# NICBP.net
KiCad netlist of a schematic drawn in EAGLE
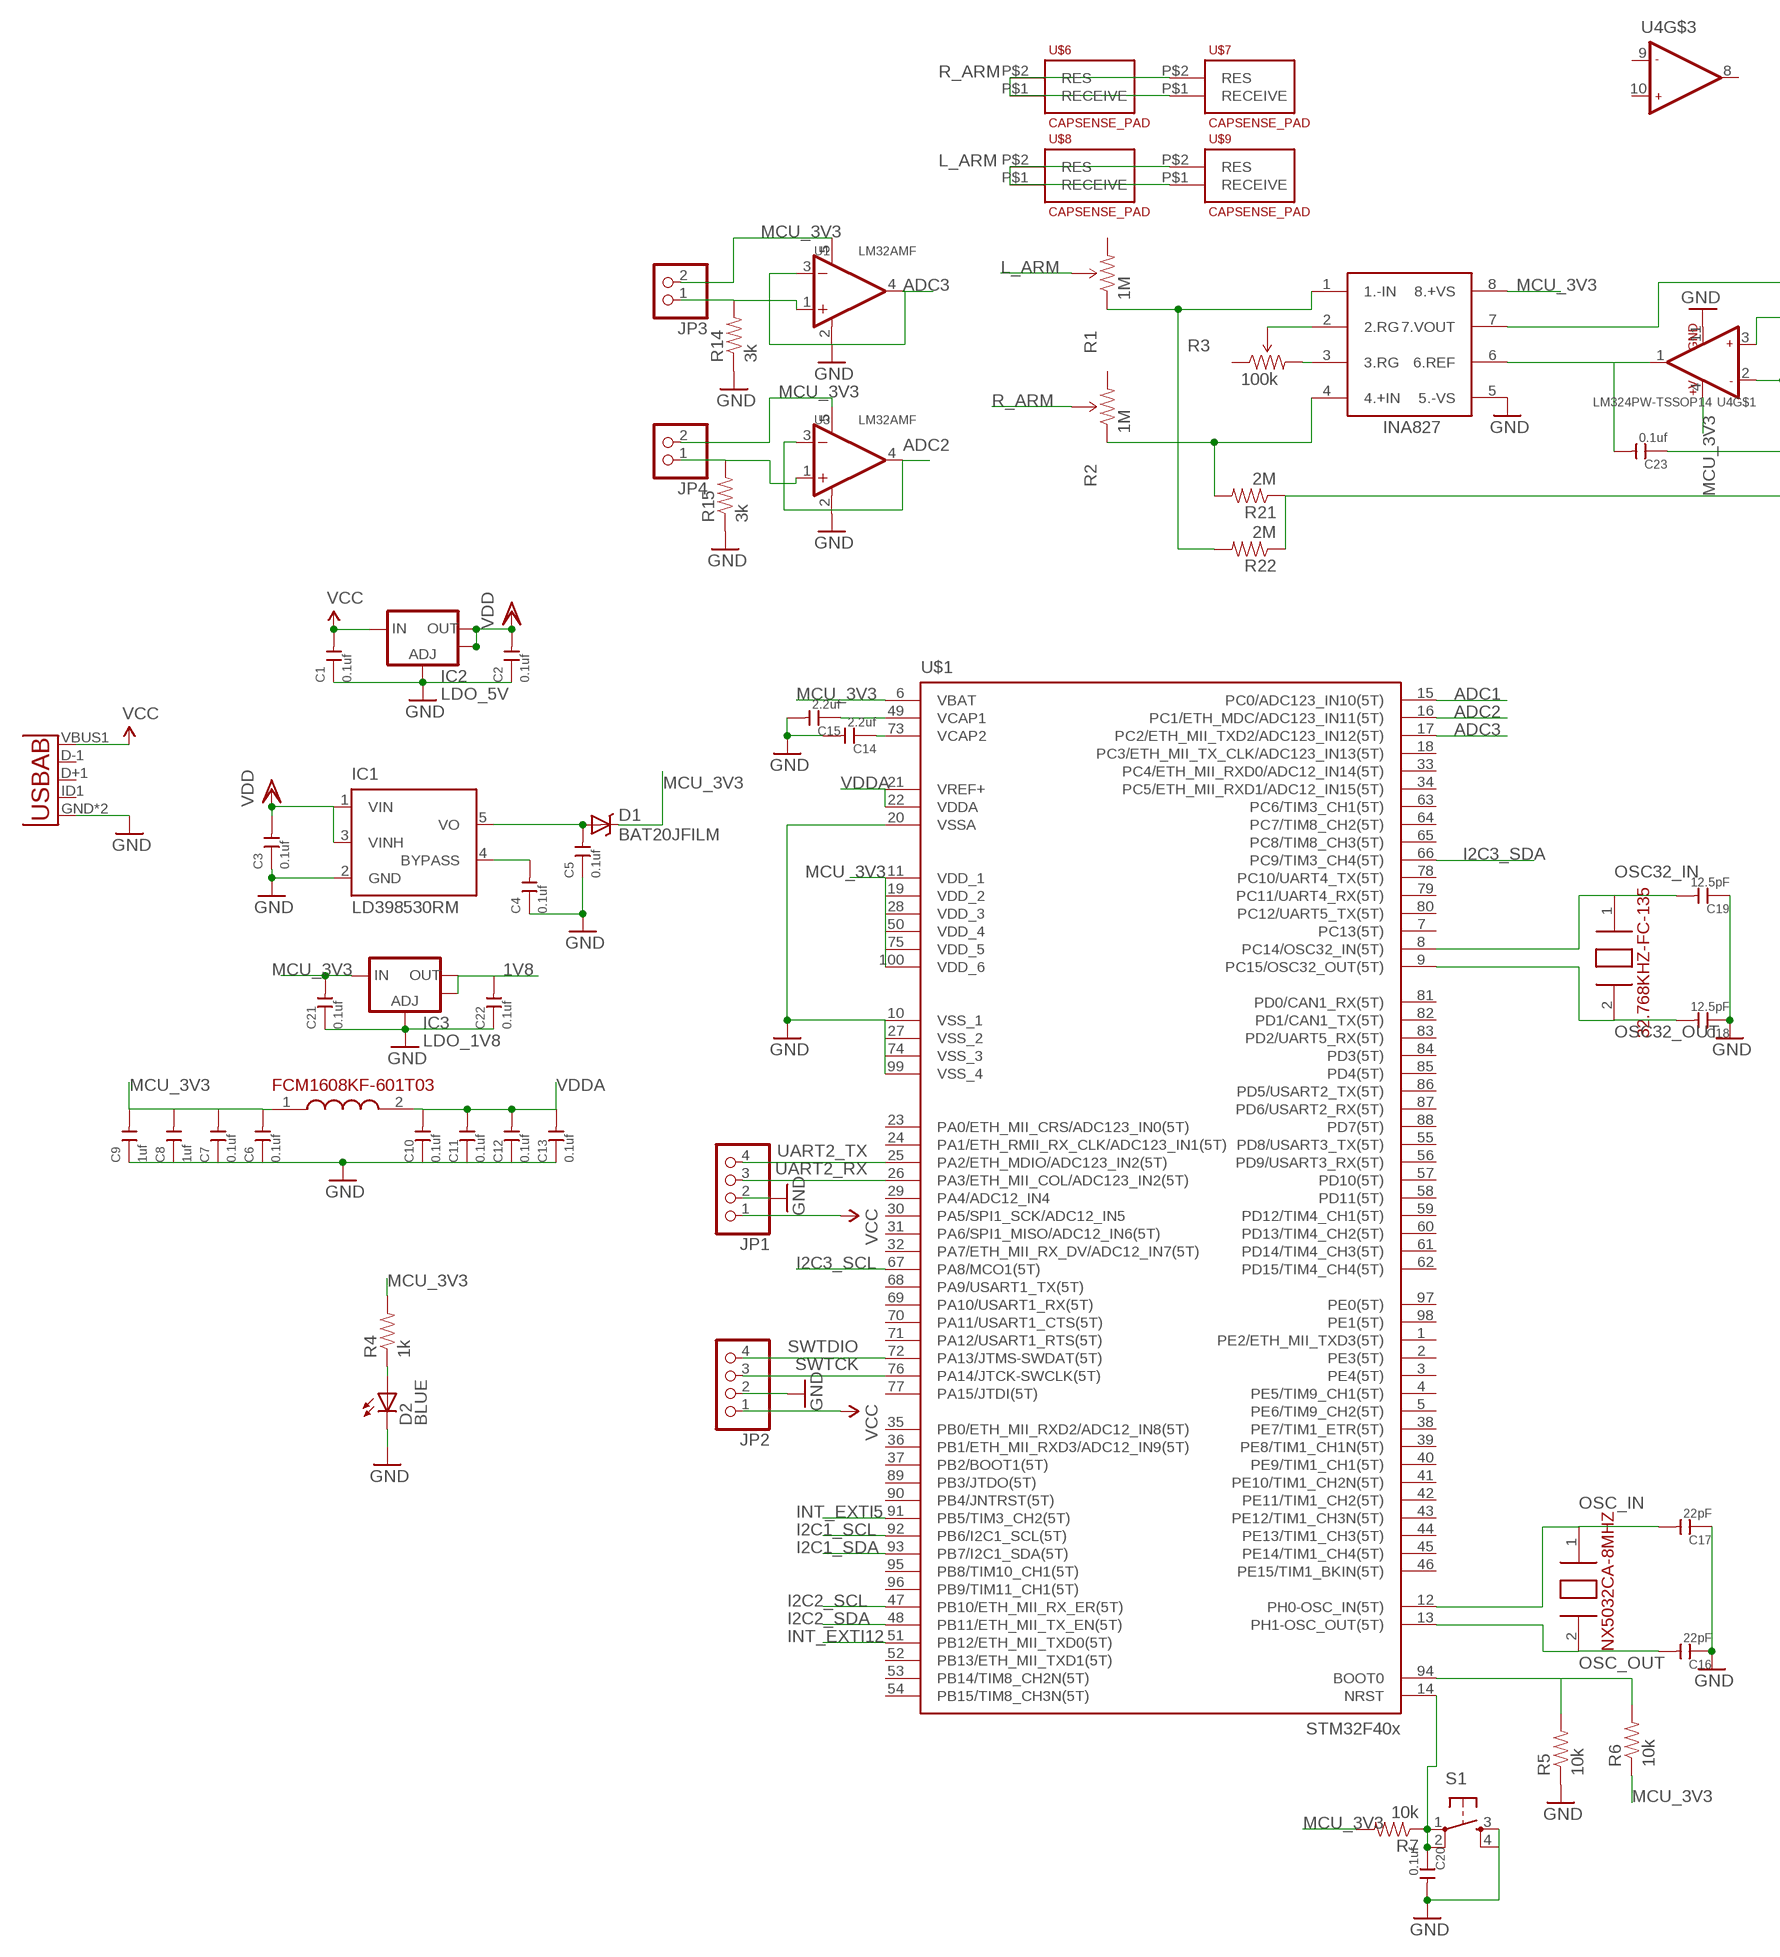
[diagram p0: schematic, sheet 1, part 1 of 2]
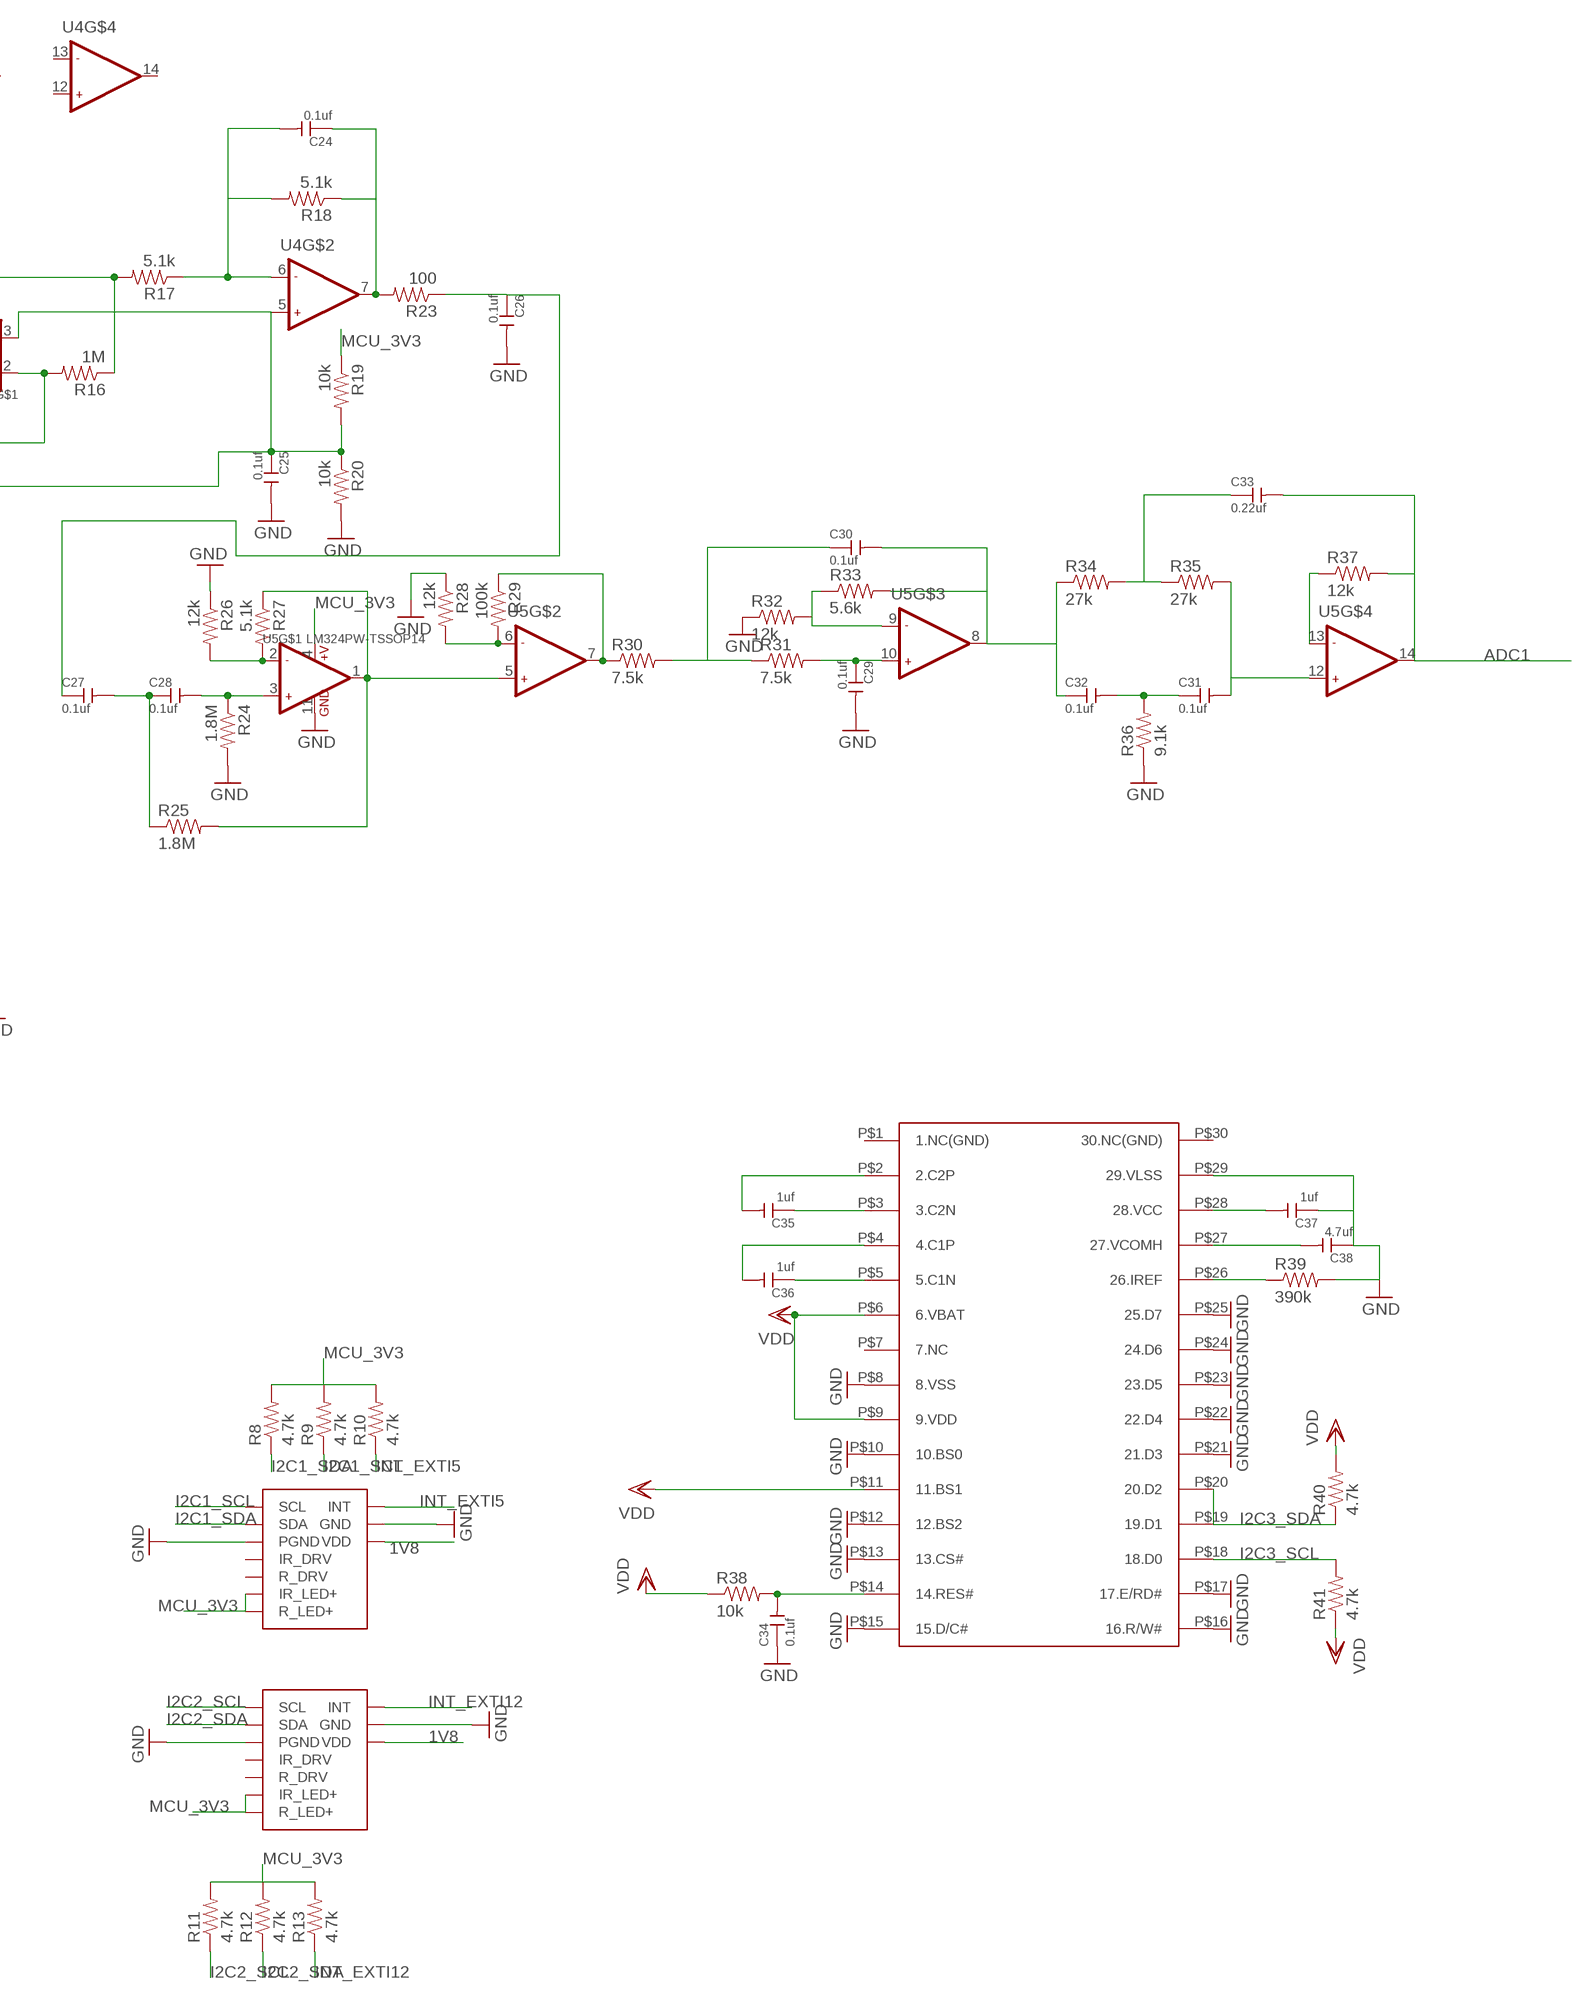
[diagram p1: schematic, sheet 1, part 2 of 2]

(export (version "E")
  (design (tool "Eeschema 10.0.6"))
  (components
    (comp (ref "C1")
      (value "0.1uf")
      (footprint "eagle-import:C0603")
      (fields (field (name "MPN") "CC0603KRX5R6BB475"))
      (libsource (lib "eagle-import") (part "CERAMIC-4.7UF-10V-10%-X5R(0603)"))
    )
    (comp (ref "C2")
      (value "0.1uf")
      (footprint "eagle-import:C0603")
      (fields (field (name "MPN") "CC0603KRX5R6BB475"))
      (libsource (lib "eagle-import") (part "CERAMIC-4.7UF-10V-10%-X5R(0603)"))
    )
    (comp (ref "C3")
      (value "0.1uf")
      (footprint "eagle-import:C0603")
      (fields (field (name "MPN") "CC0603KRX5R6BB475"))
      (libsource (lib "eagle-import") (part "CERAMIC-4.7UF-10V-10%-X5R(0603)"))
    )
    (comp (ref "C4")
      (value "0.1uf")
      (footprint "eagle-import:C0603")
      (fields (field (name "MPN") "CC0603KRX5R6BB475"))
      (libsource (lib "eagle-import") (part "CERAMIC-4.7UF-10V-10%-X5R(0603)"))
    )
    (comp (ref "C5")
      (value "0.1uf")
      (footprint "eagle-import:C0603")
      (fields (field (name "MPN") "CC0603KRX5R6BB475"))
      (libsource (lib "eagle-import") (part "CERAMIC-4.7UF-10V-10%-X5R(0603)"))
    )
    (comp (ref "C6")
      (value "0.1uf")
      (footprint "eagle-import:C0603")
      (fields (field (name "MPN") "CC0603KRX5R6BB475"))
      (libsource (lib "eagle-import") (part "CERAMIC-4.7UF-10V-10%-X5R(0603)"))
    )
    (comp (ref "C7")
      (value "0.1uf")
      (footprint "eagle-import:C0603")
      (fields (field (name "MPN") "CC0603KRX5R6BB475"))
      (libsource (lib "eagle-import") (part "CERAMIC-4.7UF-10V-10%-X5R(0603)"))
    )
    (comp (ref "C8")
      (value "1uf")
      (footprint "eagle-import:C0603")
      (fields (field (name "MPN") "CC0603KRX5R6BB475"))
      (libsource (lib "eagle-import") (part "CERAMIC-4.7UF-10V-10%-X5R(0603)"))
    )
    (comp (ref "C9")
      (value "1uf")
      (footprint "eagle-import:C0603")
      (fields (field (name "MPN") "CC0603KRX5R6BB475"))
      (libsource (lib "eagle-import") (part "CERAMIC-4.7UF-10V-10%-X5R(0603)"))
    )
    (comp (ref "C10")
      (value "0.1uf")
      (footprint "eagle-import:C0603")
      (fields (field (name "MPN") "CC0603KRX5R6BB475"))
      (libsource (lib "eagle-import") (part "CERAMIC-4.7UF-10V-10%-X5R(0603)"))
    )
    (comp (ref "C11")
      (value "0.1uf")
      (footprint "eagle-import:C0603")
      (fields (field (name "MPN") "CC0603KRX5R6BB475"))
      (libsource (lib "eagle-import") (part "CERAMIC-4.7UF-10V-10%-X5R(0603)"))
    )
    (comp (ref "C12")
      (value "0.1uf")
      (footprint "eagle-import:C0603")
      (fields (field (name "MPN") "CC0603KRX5R6BB475"))
      (libsource (lib "eagle-import") (part "CERAMIC-4.7UF-10V-10%-X5R(0603)"))
    )
    (comp (ref "C13")
      (value "0.1uf")
      (footprint "eagle-import:C0603")
      (fields (field (name "MPN") "CC0603KRX5R6BB475"))
      (libsource (lib "eagle-import") (part "CERAMIC-4.7UF-10V-10%-X5R(0603)"))
    )
    (comp (ref "C14")
      (value "2.2uf")
      (footprint "eagle-import:C0603")
      (fields (field (name "MPN") "CC0603KRX5R6BB475"))
      (libsource (lib "eagle-import") (part "CERAMIC-4.7UF-10V-10%-X5R(0603)"))
    )
    (comp (ref "C15")
      (value "2.2uf")
      (footprint "eagle-import:C0603")
      (fields (field (name "MPN") "CC0603KRX5R6BB475"))
      (libsource (lib "eagle-import") (part "CERAMIC-4.7UF-10V-10%-X5R(0603)"))
    )
    (comp (ref "C16")
      (value "22pF")
      (footprint "eagle-import:C0603")
      (fields (field (name "MPN") "CC0603KRX5R6BB475"))
      (libsource (lib "eagle-import") (part "CERAMIC-4.7UF-10V-10%-X5R(0603)"))
    )
    (comp (ref "C17")
      (value "22pF")
      (footprint "eagle-import:C0603")
      (fields (field (name "MPN") "CC0603KRX5R6BB475"))
      (libsource (lib "eagle-import") (part "CERAMIC-4.7UF-10V-10%-X5R(0603)"))
    )
    (comp (ref "C18")
      (value "12.5pF")
      (footprint "eagle-import:C0603")
      (fields (field (name "MPN") "CC0603KRX5R6BB475"))
      (libsource (lib "eagle-import") (part "CERAMIC-4.7UF-10V-10%-X5R(0603)"))
    )
    (comp (ref "C19")
      (value "12.5pF")
      (footprint "eagle-import:C0603")
      (fields (field (name "MPN") "CC0603KRX5R6BB475"))
      (libsource (lib "eagle-import") (part "CERAMIC-4.7UF-10V-10%-X5R(0603)"))
    )
    (comp (ref "C20")
      (value "0.1uf")
      (footprint "eagle-import:C0603")
      (fields (field (name "MPN") "CC0603KRX5R6BB475"))
      (libsource (lib "eagle-import") (part "CERAMIC-4.7UF-10V-10%-X5R(0603)"))
    )
    (comp (ref "C21")
      (value "0.1uf")
      (footprint "eagle-import:C0603")
      (fields (field (name "MPN") "CC0603KRX5R6BB475"))
      (libsource (lib "eagle-import") (part "CERAMIC-4.7UF-10V-10%-X5R(0603)"))
    )
    (comp (ref "C22")
      (value "0.1uf")
      (footprint "eagle-import:C0603")
      (fields (field (name "MPN") "CC0603KRX5R6BB475"))
      (libsource (lib "eagle-import") (part "CERAMIC-4.7UF-10V-10%-X5R(0603)"))
    )
    (comp (ref "C23")
      (value "0.1uf")
      (footprint "eagle-import:C0603")
      (fields (field (name "MPN") "CC0603KRX5R6BB475"))
      (libsource (lib "eagle-import") (part "CERAMIC-4.7UF-10V-10%-X5R(0603)"))
    )
    (comp (ref "C24")
      (value "0.1uf")
      (footprint "eagle-import:C0603")
      (fields (field (name "MPN") "CC0603KRX5R6BB475"))
      (libsource (lib "eagle-import") (part "CERAMIC-4.7UF-10V-10%-X5R(0603)"))
    )
    (comp (ref "C25")
      (value "0.1uf")
      (footprint "eagle-import:C0603")
      (fields (field (name "MPN") "CC0603KRX5R6BB475"))
      (libsource (lib "eagle-import") (part "CERAMIC-4.7UF-10V-10%-X5R(0603)"))
    )
    (comp (ref "C26")
      (value "0.1uf")
      (footprint "eagle-import:C0603")
      (fields (field (name "MPN") "CC0603KRX5R6BB475"))
      (libsource (lib "eagle-import") (part "CERAMIC-4.7UF-10V-10%-X5R(0603)"))
    )
    (comp (ref "C27")
      (value "0.1uf")
      (footprint "eagle-import:C0603")
      (fields (field (name "MPN") "CC0603KRX5R6BB475"))
      (libsource (lib "eagle-import") (part "CERAMIC-4.7UF-10V-10%-X5R(0603)"))
    )
    (comp (ref "C28")
      (value "0.1uf")
      (footprint "eagle-import:C0603")
      (fields (field (name "MPN") "CC0603KRX5R6BB475"))
      (libsource (lib "eagle-import") (part "CERAMIC-4.7UF-10V-10%-X5R(0603)"))
    )
    (comp (ref "C29")
      (value "0.1uf")
      (footprint "eagle-import:C0603")
      (fields (field (name "MPN") "CC0603KRX5R6BB475"))
      (libsource (lib "eagle-import") (part "CERAMIC-4.7UF-10V-10%-X5R(0603)"))
    )
    (comp (ref "C30")
      (value "0.1uf")
      (footprint "eagle-import:C0603")
      (fields (field (name "MPN") "CC0603KRX5R6BB475"))
      (libsource (lib "eagle-import") (part "CERAMIC-4.7UF-10V-10%-X5R(0603)"))
    )
    (comp (ref "C31")
      (value "0.1uf")
      (footprint "eagle-import:C0603")
      (fields (field (name "MPN") "CC0603KRX5R6BB475"))
      (libsource (lib "eagle-import") (part "CERAMIC-4.7UF-10V-10%-X5R(0603)"))
    )
    (comp (ref "C32")
      (value "0.1uf")
      (footprint "eagle-import:C0603")
      (fields (field (name "MPN") "CC0603KRX5R6BB475"))
      (libsource (lib "eagle-import") (part "CERAMIC-4.7UF-10V-10%-X5R(0603)"))
    )
    (comp (ref "C33")
      (value "0.22uf")
      (footprint "eagle-import:C0603")
      (fields (field (name "MPN") "CC0603KRX5R6BB475"))
      (libsource (lib "eagle-import") (part "CERAMIC-4.7UF-10V-10%-X5R(0603)"))
    )
    (comp (ref "C34")
      (value "0.1uf")
      (footprint "eagle-import:C0603")
      (fields (field (name "MPN") "CC0603KRX5R6BB475"))
      (libsource (lib "eagle-import") (part "CERAMIC-4.7UF-10V-10%-X5R(0603)"))
    )
    (comp (ref "C35")
      (value "1uf")
      (footprint "eagle-import:C0603")
      (fields (field (name "MPN") "CC0603KRX5R6BB475"))
      (libsource (lib "eagle-import") (part "CERAMIC-4.7UF-10V-10%-X5R(0603)"))
    )
    (comp (ref "C36")
      (value "1uf")
      (footprint "eagle-import:C0603")
      (fields (field (name "MPN") "CC0603KRX5R6BB475"))
      (libsource (lib "eagle-import") (part "CERAMIC-4.7UF-10V-10%-X5R(0603)"))
    )
    (comp (ref "C37")
      (value "1uf")
      (footprint "eagle-import:C0603")
      (fields (field (name "MPN") "CC0603KRX5R6BB475"))
      (libsource (lib "eagle-import") (part "CERAMIC-4.7UF-10V-10%-X5R(0603)"))
    )
    (comp (ref "C38")
      (value "4.7uf")
      (footprint "eagle-import:C0603")
      (fields (field (name "MPN") "CC0603KRX5R6BB475"))
      (libsource (lib "eagle-import") (part "CERAMIC-4.7UF-10V-10%-X5R(0603)"))
    )
    (comp (ref "D1")
      (value "BAT20JFILM")
      (footprint "eagle-import:SOD-323")
      (libsource (lib "eagle-import") (part "BAT20JFILM"))
    )
    (comp (ref "D2")
      (value "BLUE")
      (footprint "eagle-import:LED-0603")
      (libsource (lib "eagle-import") (part "LED-BLUE0603"))
    )
    (comp (ref "IC1")
      (value "LD398530RM")
      (footprint "eagle-import:SOT23-5L")
      (libsource (lib "eagle-import") (part "LD3985M30R"))
    )
    (comp (ref "IC2")
      (value "LDO_5V")
      (footprint "eagle-import:SOT223")
      (libsource (lib "eagle-import") (part "V_REG_LM1117SOT223"))
    )
    (comp (ref "IC3")
      (value "LDO_1V8")
      (footprint "eagle-import:SOT223")
      (libsource (lib "eagle-import") (part "V_REG_LM1117SOT223"))
    )
    (comp (ref "JP1")
      (value "PINHD-1X4")
      (footprint "eagle-import:1X04")
      (libsource (lib "eagle-import") (part "PINHD-1X4"))
    )
    (comp (ref "JP2")
      (value "PINHD-1X4")
      (footprint "eagle-import:1X04")
      (libsource (lib "eagle-import") (part "PINHD-1X4"))
    )
    (comp (ref "JP3")
      (value "PINHD-1X2")
      (footprint "eagle-import:1X02")
      (libsource (lib "eagle-import") (part "PINHD-1X2"))
    )
    (comp (ref "JP4")
      (value "PINHD-1X2")
      (footprint "eagle-import:1X02")
      (libsource (lib "eagle-import") (part "PINHD-1X2"))
    )
    (comp (ref "R1")
      (value "1M")
      (footprint "eagle-import:TRIMPOT_TC33")
      (libsource (lib "eagle-import") (part "TRIMPOT-2"))
    )
    (comp (ref "R2")
      (value "1M")
      (footprint "eagle-import:TRIMPOT_TC33")
      (libsource (lib "eagle-import") (part "TRIMPOT-2"))
    )
    (comp (ref "R3")
      (value "100k")
      (footprint "eagle-import:TRIMPOT_TC33")
      (libsource (lib "eagle-import") (part "TRIMPOT-2"))
    )
    (comp (ref "R4")
      (value "1k")
      (footprint "eagle-import:0603")
      (libsource (lib "eagle-import") (part "0OHM1/10W5%(0603)"))
    )
    (comp (ref "R5")
      (value "10k")
      (footprint "eagle-import:0603")
      (libsource (lib "eagle-import") (part "0OHM1/10W5%(0603)"))
    )
    (comp (ref "R6")
      (value "10k")
      (footprint "eagle-import:0603")
      (libsource (lib "eagle-import") (part "0OHM1/10W5%(0603)"))
    )
    (comp (ref "R7")
      (value "10k")
      (footprint "eagle-import:0603")
      (libsource (lib "eagle-import") (part "0OHM1/10W5%(0603)"))
    )
    (comp (ref "R8")
      (value "4.7k")
      (footprint "eagle-import:0603")
      (libsource (lib "eagle-import") (part "0OHM1/10W5%(0603)"))
    )
    (comp (ref "R9")
      (value "4.7k")
      (footprint "eagle-import:0603")
      (libsource (lib "eagle-import") (part "0OHM1/10W5%(0603)"))
    )
    (comp (ref "R10")
      (value "4.7k")
      (footprint "eagle-import:0603")
      (libsource (lib "eagle-import") (part "0OHM1/10W5%(0603)"))
    )
    (comp (ref "R11")
      (value "4.7k")
      (footprint "eagle-import:0603")
      (libsource (lib "eagle-import") (part "0OHM1/10W5%(0603)"))
    )
    (comp (ref "R12")
      (value "4.7k")
      (footprint "eagle-import:0603")
      (libsource (lib "eagle-import") (part "0OHM1/10W5%(0603)"))
    )
    (comp (ref "R13")
      (value "4.7k")
      (footprint "eagle-import:0603")
      (libsource (lib "eagle-import") (part "0OHM1/10W5%(0603)"))
    )
    (comp (ref "R14")
      (value "3k")
      (footprint "eagle-import:0603")
      (libsource (lib "eagle-import") (part "0OHM1/10W5%(0603)"))
    )
    (comp (ref "R15")
      (value "3k")
      (footprint "eagle-import:0603")
      (libsource (lib "eagle-import") (part "0OHM1/10W5%(0603)"))
    )
    (comp (ref "R16")
      (value "1M")
      (footprint "eagle-import:0603")
      (libsource (lib "eagle-import") (part "0OHM1/10W5%(0603)"))
    )
    (comp (ref "R17")
      (value "5.1k")
      (footprint "eagle-import:0603")
      (libsource (lib "eagle-import") (part "0OHM1/10W5%(0603)"))
    )
    (comp (ref "R18")
      (value "5.1k")
      (footprint "eagle-import:0603")
      (libsource (lib "eagle-import") (part "0OHM1/10W5%(0603)"))
    )
    (comp (ref "R19")
      (value "10k")
      (footprint "eagle-import:0603")
      (libsource (lib "eagle-import") (part "0OHM1/10W5%(0603)"))
    )
    (comp (ref "R20")
      (value "10k")
      (footprint "eagle-import:0603")
      (libsource (lib "eagle-import") (part "0OHM1/10W5%(0603)"))
    )
    (comp (ref "R21")
      (value "2M")
      (footprint "eagle-import:0603")
      (libsource (lib "eagle-import") (part "0OHM1/10W5%(0603)"))
    )
    (comp (ref "R22")
      (value "2M")
      (footprint "eagle-import:0603")
      (libsource (lib "eagle-import") (part "0OHM1/10W5%(0603)"))
    )
    (comp (ref "R23")
      (value "100")
      (footprint "eagle-import:0603")
      (libsource (lib "eagle-import") (part "0OHM1/10W5%(0603)"))
    )
    (comp (ref "R24")
      (value "1.8M")
      (footprint "eagle-import:0603")
      (libsource (lib "eagle-import") (part "0OHM1/10W5%(0603)"))
    )
    (comp (ref "R25")
      (value "1.8M")
      (footprint "eagle-import:0603")
      (libsource (lib "eagle-import") (part "0OHM1/10W5%(0603)"))
    )
    (comp (ref "R26")
      (value "12k")
      (footprint "eagle-import:0603")
      (libsource (lib "eagle-import") (part "0OHM1/10W5%(0603)"))
    )
    (comp (ref "R27")
      (value "5.1k")
      (footprint "eagle-import:0603")
      (libsource (lib "eagle-import") (part "0OHM1/10W5%(0603)"))
    )
    (comp (ref "R28")
      (value "12k")
      (footprint "eagle-import:0603")
      (libsource (lib "eagle-import") (part "0OHM1/10W5%(0603)"))
    )
    (comp (ref "R29")
      (value "100k")
      (footprint "eagle-import:0603")
      (libsource (lib "eagle-import") (part "0OHM1/10W5%(0603)"))
    )
    (comp (ref "R30")
      (value "7.5k")
      (footprint "eagle-import:0603")
      (libsource (lib "eagle-import") (part "0OHM1/10W5%(0603)"))
    )
    (comp (ref "R31")
      (value "7.5k")
      (footprint "eagle-import:0603")
      (libsource (lib "eagle-import") (part "0OHM1/10W5%(0603)"))
    )
    (comp (ref "R32")
      (value "12k")
      (footprint "eagle-import:0603")
      (libsource (lib "eagle-import") (part "0OHM1/10W5%(0603)"))
    )
    (comp (ref "R33")
      (value "5.6k")
      (footprint "eagle-import:0603")
      (libsource (lib "eagle-import") (part "0OHM1/10W5%(0603)"))
    )
    (comp (ref "R34")
      (value "27k")
      (footprint "eagle-import:0603")
      (libsource (lib "eagle-import") (part "0OHM1/10W5%(0603)"))
    )
    (comp (ref "R35")
      (value "27k")
      (footprint "eagle-import:0603")
      (libsource (lib "eagle-import") (part "0OHM1/10W5%(0603)"))
    )
    (comp (ref "R36")
      (value "9.1k")
      (footprint "eagle-import:0603")
      (libsource (lib "eagle-import") (part "0OHM1/10W5%(0603)"))
    )
    (comp (ref "R37")
      (value "12k")
      (footprint "eagle-import:0603")
      (libsource (lib "eagle-import") (part "0OHM1/10W5%(0603)"))
    )
    (comp (ref "R38")
      (value "10k")
      (footprint "eagle-import:0603")
      (libsource (lib "eagle-import") (part "0OHM1/10W5%(0603)"))
    )
    (comp (ref "R39")
      (value "390k")
      (footprint "eagle-import:0603")
      (libsource (lib "eagle-import") (part "0OHM1/10W5%(0603)"))
    )
    (comp (ref "R40")
      (value "4.7k")
      (footprint "eagle-import:0603")
      (libsource (lib "eagle-import") (part "0OHM1/10W5%(0603)"))
    )
    (comp (ref "R41")
      (value "4.7k")
      (footprint "eagle-import:0603")
      (libsource (lib "eagle-import") (part "0OHM1/10W5%(0603)"))
    )
    (comp (ref "S1")
      (value "TAC_SWITCHSMD")
      (footprint "eagle-import:TACTILE_SWITCH_SMD")
      (libsource (lib "eagle-import") (part "TAC_SWITCHSMD"))
    )
    (comp (ref "U$1")
      (value "STM32F407V")
      (footprint "eagle-import:TQFP100")
      (libsource (lib "eagle-import") (part "STM32F407V"))
    )
    (comp (ref "U$2")
      (value "NX5032CA-8MHZ")
      (footprint "eagle-import:NX5032CA-8MHZ")
      (libsource (lib "eagle-import") (part "NX5032CA-8MHZ"))
    )
    (comp (ref "U$3")
      (value "FCM1608KF-601T03")
      (footprint "eagle-import:FCM1608KF-601T03")
      (libsource (lib "eagle-import") (part "FCM1608KF-601T03"))
    )
    (comp (ref "U$4")
      (value "32.768KHZ-FC-135")
      (footprint "eagle-import:32.768KHZ-FC-135")
      (libsource (lib "eagle-import") (part "32.768KHZ-FC-135"))
    )
    (comp (ref "U$5")
      (value "INA827")
      (footprint "eagle-import:INA827")
      (libsource (lib "eagle-import") (part "INA827"))
    )
    (comp (ref "U$6")
      (value "CAPSENSE_PAD")
      (footprint "eagle-import:CAPSENSE_PAD")
      (libsource (lib "eagle-import") (part "CAPSENSE_PAD"))
    )
    (comp (ref "U$7")
      (value "CAPSENSE_PAD")
      (footprint "eagle-import:CAPSENSE_PAD")
      (libsource (lib "eagle-import") (part "CAPSENSE_PAD"))
    )
    (comp (ref "U$8")
      (value "CAPSENSE_PAD")
      (footprint "eagle-import:CAPSENSE_PAD")
      (libsource (lib "eagle-import") (part "CAPSENSE_PAD"))
    )
    (comp (ref "U$9")
      (value "CAPSENSE_PAD")
      (footprint "eagle-import:CAPSENSE_PAD")
      (libsource (lib "eagle-import") (part "CAPSENSE_PAD"))
    )
    (comp (ref "U$10")
      (value "MAX30100")
      (footprint "eagle-import:MAX30100")
      (libsource (lib "eagle-import") (part "MAX30100"))
    )
    (comp (ref "U$11")
      (value "MAX30100")
      (footprint "eagle-import:MAX30100")
      (libsource (lib "eagle-import") (part "MAX30100"))
    )
    (comp (ref "U$12")
      (value "ER-OLED0.96")
      (footprint "eagle-import:ER-OLED0.96")
      (libsource (lib "eagle-import") (part "ER-OLED0.96"))
    )
    (comp (ref "U1")
      (value "LM32AMF")
      (footprint "eagle-import:SOT-23-5")
      (fields (field (name "MPN") "LM321MF"))
      (libsource (lib "eagle-import") (part "AMPLIFIER-LM321MF(SOT23-5)"))
    )
    (comp (ref "U2")
      (value "USB\"\"")
      (footprint "eagle-import:USB-MICRO-SMD")
      (libsource (lib "eagle-import") (part "USB{dblquote}{dblquote}"))
    )
    (comp (ref "U3")
      (value "LM32AMF")
      (footprint "eagle-import:SOT-23-5")
      (fields (field (name "MPN") "LM321MF"))
      (libsource (lib "eagle-import") (part "AMPLIFIER-LM321MF(SOT23-5)"))
    )
    (comp (ref "U4")
      (value "LM324PW-TSSOP14")
      (footprint "eagle-import:TSSOP14-0.65-5X4.4MM")
      (fields (field (name "MPN") "LM324PW"))
      (libsource (lib "eagle-import") (part "AMPLIFIER-LM324PW(TSSOP14)"))
    )
    (comp (ref "U5")
      (value "LM324PW-TSSOP14")
      (footprint "eagle-import:TSSOP14-0.65-5X4.4MM")
      (fields (field (name "MPN") "LM324PW"))
      (libsource (lib "eagle-import") (part "AMPLIFIER-LM324PW(TSSOP14)"))
    )
  )
  (nets
    (net (code "1") (name "/1V8") (class "Default")
      (node (ref "C22") (pin "2") (pinfunction "2_2") (pintype "passive"))
      (node (ref "IC3") (pin "2") (pinfunction "OUT_2") (pintype "output"))
      (node (ref "IC3") (pin "4") (pinfunction "OUT_4") (pintype "output"))
      (node (ref "U$10") (pin "11") (pinfunction "VDD_11") (pintype "bidirectional"))
      (node (ref "U$11") (pin "11") (pinfunction "VDD_11") (pintype "bidirectional"))
    )
    (net (code "2") (name "/ADC1") (class "Default")
      (node (ref "C33") (pin "2") (pinfunction "2_2") (pintype "passive"))
      (node (ref "R37") (pin "2") (pinfunction "2_2") (pintype "passive"))
      (node (ref "U$1") (pin "15") (pinfunction "PC0/ADC123_IN10(5T)_15") (pintype "bidirectional"))
      (node (ref "U5") (pin "14") (pinfunction "OUT2_14") (pintype "output"))
    )
    (net (code "3") (name "/ADC2") (class "Default")
      (node (ref "U$1") (pin "16") (pinfunction "PC1/ETH_MDC/ADC123_IN11(5T)_16") (pintype "bidirectional"))
      (node (ref "U3") (pin "3") (pinfunction "IN-_3") (pintype "input"))
      (node (ref "U3") (pin "4") (pinfunction "OUT_4") (pintype "output"))
    )
    (net (code "4") (name "/ADC3") (class "Default")
      (node (ref "U$1") (pin "17") (pinfunction "PC2/ETH_MII_TXD2/ADC123_IN12(5T)_17") (pintype "bidirectional"))
      (node (ref "U1") (pin "3") (pinfunction "IN-_3") (pintype "input"))
      (node (ref "U1") (pin "4") (pinfunction "OUT_4") (pintype "output"))
    )
    (net (code "5") (name "/I2C1_SCL") (class "Default")
      (node (ref "R9") (pin "1") (pinfunction "1_1") (pintype "passive"))
      (node (ref "U$1") (pin "92") (pinfunction "PB6/I2C1_SCL(5T)_92") (pintype "bidirectional"))
      (node (ref "U$10") (pin "2") (pinfunction "SCL_2") (pintype "bidirectional"))
    )
    (net (code "6") (name "/I2C1_SDA") (class "Default")
      (node (ref "R8") (pin "1") (pinfunction "1_1") (pintype "passive"))
      (node (ref "U$1") (pin "93") (pinfunction "PB7/I2C1_SDA(5T)_93") (pintype "bidirectional"))
      (node (ref "U$10") (pin "3") (pinfunction "SDA_3") (pintype "bidirectional"))
    )
    (net (code "7") (name "/I2C2_SCL") (class "Default")
      (node (ref "R11") (pin "1") (pinfunction "1_1") (pintype "passive"))
      (node (ref "U$1") (pin "47") (pinfunction "PB10/ETH_MII_RX_ER(5T)_47") (pintype "bidirectional"))
      (node (ref "U$11") (pin "2") (pinfunction "SCL_2") (pintype "bidirectional"))
    )
    (net (code "8") (name "/I2C2_SDA") (class "Default")
      (node (ref "R12") (pin "1") (pinfunction "1_1") (pintype "passive"))
      (node (ref "U$1") (pin "48") (pinfunction "PB11/ETH_MII_TX_EN(5T)_48") (pintype "bidirectional"))
      (node (ref "U$11") (pin "3") (pinfunction "SDA_3") (pintype "bidirectional"))
    )
    (net (code "9") (name "/I2C3_SCL") (class "Default")
      (node (ref "R41") (pin "2") (pinfunction "2_2") (pintype "passive"))
      (node (ref "U$1") (pin "67") (pinfunction "PA8/MCO1(5T)_67") (pintype "bidirectional"))
      (node (ref "U$12") (pin "P$18") (pinfunction "18.D0_P$18") (pintype "bidirectional"))
    )
    (net (code "10") (name "/I2C3_SDA") (class "Default")
      (node (ref "R40") (pin "1") (pinfunction "1_1") (pintype "passive"))
      (node (ref "U$1") (pin "66") (pinfunction "PC9/TIM3_CH4(5T)_66") (pintype "bidirectional"))
      (node (ref "U$12") (pin "P$19") (pinfunction "19.D1_P$19") (pintype "bidirectional"))
      (node (ref "U$12") (pin "P$20") (pinfunction "20.D2_P$20") (pintype "bidirectional"))
    )
    (net (code "11") (name "/INT_EXTI5") (class "Default")
      (node (ref "R10") (pin "1") (pinfunction "1_1") (pintype "passive"))
      (node (ref "U$1") (pin "91") (pinfunction "PB5/TIM3_CH2(5T)_91") (pintype "bidirectional"))
      (node (ref "U$10") (pin "13") (pinfunction "INT_13") (pintype "bidirectional"))
    )
    (net (code "12") (name "/INT_EXTI12") (class "Default")
      (node (ref "R13") (pin "1") (pinfunction "1_1") (pintype "passive"))
      (node (ref "U$1") (pin "51") (pinfunction "PB12/ETH_MII_TXD0(5T)_51") (pintype "bidirectional"))
      (node (ref "U$11") (pin "13") (pinfunction "INT_13") (pintype "bidirectional"))
    )
    (net (code "13") (name "/L_ARM") (class "Default")
      (node (ref "R1") (pin "2") (pinfunction "WIPER_2") (pintype "passive"))
      (node (ref "U$8") (pin "P$1") (pinfunction "RECEIVE_P$1") (pintype "bidirectional"))
      (node (ref "U$8") (pin "P$2") (pinfunction "RES_P$2") (pintype "bidirectional"))
      (node (ref "U$9") (pin "P$1") (pinfunction "RECEIVE_P$1") (pintype "bidirectional"))
      (node (ref "U$9") (pin "P$2") (pinfunction "RES_P$2") (pintype "bidirectional"))
    )
    (net (code "14") (name "/MCU_3V3") (class "Default")
      (node (ref "C21") (pin "2") (pinfunction "2_2") (pintype "passive"))
      (node (ref "C6") (pin "2") (pinfunction "2_2") (pintype "passive"))
      (node (ref "C7") (pin "2") (pinfunction "2_2") (pintype "passive"))
      (node (ref "C8") (pin "2") (pinfunction "2_2") (pintype "passive"))
      (node (ref "C9") (pin "2") (pinfunction "2_2") (pintype "passive"))
      (node (ref "D1") (pin "1") (pinfunction "C_1") (pintype "passive"))
      (node (ref "IC3") (pin "3") (pinfunction "IN_3") (pintype "input"))
      (node (ref "JP3") (pin "2") (pinfunction "2_2") (pintype "passive"))
      (node (ref "JP4") (pin "2") (pinfunction "2_2") (pintype "passive"))
      (node (ref "R10") (pin "2") (pinfunction "2_2") (pintype "passive"))
      (node (ref "R11") (pin "2") (pinfunction "2_2") (pintype "passive"))
      (node (ref "R12") (pin "2") (pinfunction "2_2") (pintype "passive"))
      (node (ref "R13") (pin "2") (pinfunction "2_2") (pintype "passive"))
      (node (ref "R19") (pin "1") (pinfunction "1_1") (pintype "passive"))
      (node (ref "R4") (pin "2") (pinfunction "2_2") (pintype "passive"))
      (node (ref "R6") (pin "1") (pinfunction "1_1") (pintype "passive"))
      (node (ref "R7") (pin "2") (pinfunction "2_2") (pintype "passive"))
      (node (ref "R8") (pin "2") (pinfunction "2_2") (pintype "passive"))
      (node (ref "R9") (pin "2") (pinfunction "2_2") (pintype "passive"))
      (node (ref "U$1") (pin "100") (pinfunction "VDD_6_100") (pintype "bidirectional"))
      (node (ref "U$1") (pin "11") (pinfunction "VDD_1_11") (pintype "bidirectional"))
      (node (ref "U$1") (pin "19") (pinfunction "VDD_2_19") (pintype "bidirectional"))
      (node (ref "U$1") (pin "28") (pinfunction "VDD_3_28") (pintype "bidirectional"))
      (node (ref "U$1") (pin "50") (pinfunction "VDD_4_50") (pintype "bidirectional"))
      (node (ref "U$1") (pin "6") (pinfunction "VBAT_6") (pintype "bidirectional"))
      (node (ref "U$1") (pin "75") (pinfunction "VDD_5_75") (pintype "bidirectional"))
      (node (ref "U$10") (pin "10") (pinfunction "IR_LED+_10") (pintype "bidirectional"))
      (node (ref "U$10") (pin "9") (pinfunction "R_LED+_9") (pintype "bidirectional"))
      (node (ref "U$11") (pin "10") (pinfunction "IR_LED+_10") (pintype "bidirectional"))
      (node (ref "U$11") (pin "9") (pinfunction "R_LED+_9") (pintype "bidirectional"))
      (node (ref "U$3") (pin "1") (pinfunction "1.IN_1") (pintype "bidirectional"))
      (node (ref "U$5") (pin "8") (pinfunction "8.+VS_8") (pintype "bidirectional"))
      (node (ref "U1") (pin "5") (pinfunction "V+_5") (pintype "power_in"))
      (node (ref "U3") (pin "5") (pinfunction "V+_5") (pintype "power_in"))
      (node (ref "U4") (pin "4") (pinfunction "+V_4") (pintype "power_in"))
      (node (ref "U5") (pin "4") (pinfunction "+V_4") (pintype "power_in"))
    )
    (net (code "15") (name "/OSC32_IN") (class "Default")
      (node (ref "C19") (pin "2") (pinfunction "2_2") (pintype "passive"))
      (node (ref "U$1") (pin "8") (pinfunction "PC14/OSC32_IN(5T)_8") (pintype "bidirectional"))
      (node (ref "U$4") (pin "1") (pinfunction "1.XIN_1") (pintype "bidirectional"))
    )
    (net (code "16") (name "/OSC32_OUT") (class "Default")
      (node (ref "C18") (pin "2") (pinfunction "2_2") (pintype "passive"))
      (node (ref "U$1") (pin "9") (pinfunction "PC15/OSC32_OUT(5T)_9") (pintype "bidirectional"))
      (node (ref "U$4") (pin "2") (pinfunction "2.XIN_2") (pintype "bidirectional"))
    )
    (net (code "17") (name "/OSC_IN") (class "Default")
      (node (ref "C17") (pin "2") (pinfunction "2_2") (pintype "passive"))
      (node (ref "U$1") (pin "12") (pinfunction "PH0-OSC_IN(5T)_12") (pintype "bidirectional"))
      (node (ref "U$2") (pin "1") (pinfunction "1.XIN_1") (pintype "bidirectional"))
    )
    (net (code "18") (name "/OSC_OUT") (class "Default")
      (node (ref "C16") (pin "2") (pinfunction "2_2") (pintype "passive"))
      (node (ref "U$1") (pin "13") (pinfunction "PH1-OSC_OUT(5T)_13") (pintype "bidirectional"))
      (node (ref "U$2") (pin "2") (pinfunction "2.XOUT_2") (pintype "bidirectional"))
    )
    (net (code "19") (name "/R_ARM") (class "Default")
      (node (ref "R2") (pin "2") (pinfunction "WIPER_2") (pintype "passive"))
      (node (ref "U$6") (pin "P$1") (pinfunction "RECEIVE_P$1") (pintype "bidirectional"))
      (node (ref "U$6") (pin "P$2") (pinfunction "RES_P$2") (pintype "bidirectional"))
      (node (ref "U$7") (pin "P$1") (pinfunction "RECEIVE_P$1") (pintype "bidirectional"))
      (node (ref "U$7") (pin "P$2") (pinfunction "RES_P$2") (pintype "bidirectional"))
    )
    (net (code "20") (name "/SWTCK") (class "Default")
      (node (ref "JP2") (pin "3") (pinfunction "3_3") (pintype "passive"))
      (node (ref "U$1") (pin "76") (pinfunction "PA14/JTCK-SWCLK(5T)_76") (pintype "bidirectional"))
    )
    (net (code "21") (name "/SWTDIO") (class "Default")
      (node (ref "JP2") (pin "4") (pinfunction "4_4") (pintype "passive"))
      (node (ref "U$1") (pin "72") (pinfunction "PA13/JTMS-SWDAT(5T)_72") (pintype "bidirectional"))
    )
    (net (code "22") (name "/UART2_RX") (class "Default")
      (node (ref "JP1") (pin "3") (pinfunction "3_3") (pintype "passive"))
      (node (ref "U$1") (pin "26") (pinfunction "PA3/ETH_MII_COL/ADC123_IN2(5T)_26") (pintype "bidirectional"))
    )
    (net (code "23") (name "/UART2_TX") (class "Default")
      (node (ref "JP1") (pin "4") (pinfunction "4_4") (pintype "passive"))
      (node (ref "U$1") (pin "25") (pinfunction "PA2/ETH_MDIO/ADC123_IN2(5T)_25") (pintype "bidirectional"))
    )
    (net (code "24") (name "/VDDA") (class "Default")
      (node (ref "C10") (pin "2") (pinfunction "2_2") (pintype "passive"))
      (node (ref "C11") (pin "2") (pinfunction "2_2") (pintype "passive"))
      (node (ref "C12") (pin "2") (pinfunction "2_2") (pintype "passive"))
      (node (ref "C13") (pin "2") (pinfunction "2_2") (pintype "passive"))
      (node (ref "U$1") (pin "21") (pinfunction "VREF+_21") (pintype "bidirectional"))
      (node (ref "U$1") (pin "22") (pinfunction "VDDA_22") (pintype "bidirectional"))
      (node (ref "U$3") (pin "2") (pinfunction "2.OUT_2") (pintype "bidirectional"))
    )
    (net (code "25") (name "GND") (class "Default")
      (node (ref "C1") (pin "1") (pinfunction "1_1") (pintype "passive"))
      (node (ref "C10") (pin "1") (pinfunction "1_1") (pintype "passive"))
      (node (ref "C11") (pin "1") (pinfunction "1_1") (pintype "passive"))
      (node (ref "C12") (pin "1") (pinfunction "1_1") (pintype "passive"))
      (node (ref "C13") (pin "1") (pinfunction "1_1") (pintype "passive"))
      (node (ref "C14") (pin "2") (pinfunction "2_2") (pintype "passive"))
      (node (ref "C15") (pin "2") (pinfunction "2_2") (pintype "passive"))
      (node (ref "C16") (pin "1") (pinfunction "1_1") (pintype "passive"))
      (node (ref "C17") (pin "1") (pinfunction "1_1") (pintype "passive"))
      (node (ref "C18") (pin "1") (pinfunction "1_1") (pintype "passive"))
      (node (ref "C19") (pin "1") (pinfunction "1_1") (pintype "passive"))
      (node (ref "C2") (pin "1") (pinfunction "1_1") (pintype "passive"))
      (node (ref "C20") (pin "2") (pinfunction "2_2") (pintype "passive"))
      (node (ref "C21") (pin "1") (pinfunction "1_1") (pintype "passive"))
      (node (ref "C22") (pin "1") (pinfunction "1_1") (pintype "passive"))
      (node (ref "C25") (pin "2") (pinfunction "2_2") (pintype "passive"))
      (node (ref "C26") (pin "2") (pinfunction "2_2") (pintype "passive"))
      (node (ref "C29") (pin "2") (pinfunction "2_2") (pintype "passive"))
      (node (ref "C3") (pin "1") (pinfunction "1_1") (pintype "passive"))
      (node (ref "C34") (pin "1") (pinfunction "1_1") (pintype "passive"))
      (node (ref "C37") (pin "1") (pinfunction "1_1") (pintype "passive"))
      (node (ref "C38") (pin "1") (pinfunction "1_1") (pintype "passive"))
      (node (ref "C4") (pin "1") (pinfunction "1_1") (pintype "passive"))
      (node (ref "C5") (pin "1") (pinfunction "1_1") (pintype "passive"))
      (node (ref "C6") (pin "1") (pinfunction "1_1") (pintype "passive"))
      (node (ref "C7") (pin "1") (pinfunction "1_1") (pintype "passive"))
      (node (ref "C8") (pin "1") (pinfunction "1_1") (pintype "passive"))
      (node (ref "C9") (pin "1") (pinfunction "1_1") (pintype "passive"))
      (node (ref "D2") (pin "C") (pinfunction "C_C") (pintype "passive"))
      (node (ref "IC1") (pin "2") (pinfunction "GND_2") (pintype "power_in"))
      (node (ref "IC2") (pin "1") (pinfunction "ADJ_1") (pintype "input"))
      (node (ref "IC3") (pin "1") (pinfunction "ADJ_1") (pintype "input"))
      (node (ref "JP1") (pin "2") (pinfunction "2_2") (pintype "passive"))
      (node (ref "JP2") (pin "2") (pinfunction "2_2") (pintype "passive"))
      (node (ref "R14") (pin "1") (pinfunction "1_1") (pintype "passive"))
      (node (ref "R15") (pin "1") (pinfunction "1_1") (pintype "passive"))
      (node (ref "R20") (pin "2") (pinfunction "2_2") (pintype "passive"))
      (node (ref "R24") (pin "2") (pinfunction "2_2") (pintype "passive"))
      (node (ref "R26") (pin "1") (pinfunction "1_1") (pintype "passive"))
      (node (ref "R28") (pin "1") (pinfunction "1_1") (pintype "passive"))
      (node (ref "R32") (pin "1") (pinfunction "1_1") (pintype "passive"))
      (node (ref "R36") (pin "1") (pinfunction "1_1") (pintype "passive"))
      (node (ref "R39") (pin "2") (pinfunction "2_2") (pintype "passive"))
      (node (ref "R5") (pin "1") (pinfunction "1_1") (pintype "passive"))
      (node (ref "S1") (pin "3") (pinfunction "3_3") (pintype "passive"))
      (node (ref "S1") (pin "4") (pinfunction "4_4") (pintype "passive"))
      (node (ref "U$1") (pin "10") (pinfunction "VSS_1_10") (pintype "bidirectional"))
      (node (ref "U$1") (pin "20") (pinfunction "VSSA_20") (pintype "bidirectional"))
      (node (ref "U$1") (pin "27") (pinfunction "VSS_2_27") (pintype "bidirectional"))
      (node (ref "U$1") (pin "74") (pinfunction "VSS_3_74") (pintype "bidirectional"))
      (node (ref "U$1") (pin "99") (pinfunction "VSS_4_99") (pintype "bidirectional"))
      (node (ref "U$10") (pin "12") (pinfunction "GND_12") (pintype "bidirectional"))
      (node (ref "U$10") (pin "4") (pinfunction "PGND_4") (pintype "bidirectional"))
      (node (ref "U$11") (pin "12") (pinfunction "GND_12") (pintype "bidirectional"))
      (node (ref "U$11") (pin "4") (pinfunction "PGND_4") (pintype "bidirectional"))
      (node (ref "U$12") (pin "P$10") (pinfunction "10.BS0_P$10") (pintype "bidirectional"))
      (node (ref "U$12") (pin "P$12") (pinfunction "12.BS2_P$12") (pintype "bidirectional"))
      (node (ref "U$12") (pin "P$13") (pinfunction "13.CS#_P$13") (pintype "bidirectional"))
      (node (ref "U$12") (pin "P$15") (pinfunction "15.D/C#_P$15") (pintype "bidirectional"))
      (node (ref "U$12") (pin "P$16") (pinfunction "16.R/W#_P$16") (pintype "bidirectional"))
      (node (ref "U$12") (pin "P$17") (pinfunction "17.E/RD#_P$17") (pintype "bidirectional"))
      (node (ref "U$12") (pin "P$21") (pinfunction "21.D3_P$21") (pintype "bidirectional"))
      (node (ref "U$12") (pin "P$22") (pinfunction "22.D4_P$22") (pintype "bidirectional"))
      (node (ref "U$12") (pin "P$23") (pinfunction "23.D5_P$23") (pintype "bidirectional"))
      (node (ref "U$12") (pin "P$24") (pinfunction "24.D6_P$24") (pintype "bidirectional"))
      (node (ref "U$12") (pin "P$25") (pinfunction "25.D7_P$25") (pintype "bidirectional"))
      (node (ref "U$12") (pin "P$29") (pinfunction "29.VLSS_P$29") (pintype "bidirectional"))
      (node (ref "U$12") (pin "P$8") (pinfunction "8.VSS_P$8") (pintype "bidirectional"))
      (node (ref "U$5") (pin "5") (pinfunction "5.-VS_5") (pintype "bidirectional"))
      (node (ref "U1") (pin "2") (pinfunction "V-_2") (pintype "power_in"))
      (node (ref "U2") (pin "GND") (pinfunction "GND_GND") (pintype "bidirectional"))
      (node (ref "U2") (pin "GND1") (pinfunction "GND_GND1") (pintype "bidirectional"))
      (node (ref "U3") (pin "2") (pinfunction "V-_2") (pintype "power_in"))
      (node (ref "U4") (pin "11") (pinfunction "GND_11") (pintype "power_in"))
      (node (ref "U5") (pin "11") (pinfunction "GND_11") (pintype "power_in"))
    )
    (net (code "26") (name "Net-(C26-Pad1)") (class "Default")
      (node (ref "C26") (pin "1") (pinfunction "1_1") (pintype "passive"))
      (node (ref "C27") (pin "1") (pinfunction "1_1") (pintype "passive"))
      (node (ref "R23") (pin "1") (pinfunction "1_1") (pintype "passive"))
    )
    (net (code "27") (name "Net-(C27-Pad2)") (class "Default")
      (node (ref "C27") (pin "2") (pinfunction "2_2") (pintype "passive"))
      (node (ref "C28") (pin "1") (pinfunction "1_1") (pintype "passive"))
      (node (ref "R25") (pin "1") (pinfunction "1_1") (pintype "passive"))
    )
    (net (code "28") (name "Net-(C30-Pad1)") (class "Default")
      (node (ref "C30") (pin "1") (pinfunction "1_1") (pintype "passive"))
      (node (ref "R30") (pin "2") (pinfunction "2_2") (pintype "passive"))
      (node (ref "R31") (pin "1") (pinfunction "1_1") (pintype "passive"))
    )
    (net (code "29") (name "Net-(C31-Pad1)") (class "Default")
      (node (ref "C31") (pin "1") (pinfunction "1_1") (pintype "passive"))
      (node (ref "C32") (pin "2") (pinfunction "2_2") (pintype "passive"))
      (node (ref "R36") (pin "2") (pinfunction "2_2") (pintype "passive"))
    )
    (net (code "30") (name "Net-(C33-Pad1)") (class "Default")
      (node (ref "C33") (pin "1") (pinfunction "1_1") (pintype "passive"))
      (node (ref "R34") (pin "2") (pinfunction "2_2") (pintype "passive"))
      (node (ref "R35") (pin "1") (pinfunction "1_1") (pintype "passive"))
    )
    (net (code "31") (name "Net-(D1-A)") (class "Default")
      (node (ref "C5") (pin "2") (pinfunction "2_2") (pintype "passive"))
      (node (ref "D1") (pin "2") (pinfunction "A_2") (pintype "passive"))
      (node (ref "IC1") (pin "5") (pinfunction "VO_5") (pintype "output"))
    )
    (net (code "32") (name "Net-(D2-PadA)") (class "Default")
      (node (ref "D2") (pin "A") (pinfunction "A_A") (pintype "passive"))
      (node (ref "R4") (pin "1") (pinfunction "1_1") (pintype "passive"))
    )
    (net (code "33") (name "Net-(IC1-BYPASS)") (class "Default")
      (node (ref "C4") (pin "2") (pinfunction "2_2") (pintype "passive"))
      (node (ref "IC1") (pin "4") (pinfunction "BYPASS_4") (pintype "passive"))
    )
    (net (code "34") (name "Net-(R1-CCW)") (class "Default")
      (node (ref "R1") (pin "1") (pinfunction "CCW_1") (pintype "passive"))
      (node (ref "R22") (pin "2") (pinfunction "2_2") (pintype "passive"))
      (node (ref "U$5") (pin "1") (pinfunction "1.-IN_1") (pintype "bidirectional"))
    )
    (net (code "35") (name "Net-(R2-CCW)") (class "Default")
      (node (ref "R2") (pin "1") (pinfunction "CCW_1") (pintype "passive"))
      (node (ref "R21") (pin "2") (pinfunction "2_2") (pintype "passive"))
      (node (ref "U$5") (pin "4") (pinfunction "4.+IN_4") (pintype "bidirectional"))
    )
    (net (code "36") (name "Net-(R3-CW)") (class "Default")
      (node (ref "R3") (pin "3") (pinfunction "CW_3") (pintype "passive"))
      (node (ref "U$5") (pin "3") (pinfunction "3.RG_3") (pintype "bidirectional"))
    )
    (net (code "37") (name "Net-(R3-WIPER)") (class "Default")
      (node (ref "R3") (pin "2") (pinfunction "WIPER_2") (pintype "passive"))
      (node (ref "U$5") (pin "2") (pinfunction "2.RG_2") (pintype "bidirectional"))
    )
    (net (code "38") (name "Net-(U$1-BOOT0)") (class "Default")
      (node (ref "R5") (pin "2") (pinfunction "2_2") (pintype "passive"))
      (node (ref "R6") (pin "2") (pinfunction "2_2") (pintype "passive"))
      (node (ref "U$1") (pin "94") (pinfunction "BOOT0_94") (pintype "bidirectional"))
    )
    (net (code "39") (name "Net-(U$1-NRST)") (class "Default")
      (node (ref "C20") (pin "1") (pinfunction "1_1") (pintype "passive"))
      (node (ref "R7") (pin "1") (pinfunction "1_1") (pintype "passive"))
      (node (ref "S1") (pin "1") (pinfunction "1_1") (pintype "passive"))
      (node (ref "S1") (pin "2") (pinfunction "2_2") (pintype "passive"))
      (node (ref "U$1") (pin "14") (pinfunction "NRST_14") (pintype "bidirectional"))
    )
    (net (code "40") (name "Net-(U$1-VCAP1)") (class "Default")
      (node (ref "C15") (pin "1") (pinfunction "1_1") (pintype "passive"))
      (node (ref "U$1") (pin "49") (pinfunction "VCAP1_49") (pintype "bidirectional"))
    )
    (net (code "41") (name "Net-(U$1-VCAP2)") (class "Default")
      (node (ref "C14") (pin "1") (pinfunction "1_1") (pintype "passive"))
      (node (ref "U$1") (pin "73") (pinfunction "VCAP2_73") (pintype "bidirectional"))
    )
    (net (code "42") (name "Net-(U$5-6.REF)") (class "Default")
      (node (ref "C23") (pin "2") (pinfunction "2_2") (pintype "passive"))
      (node (ref "U$5") (pin "6") (pinfunction "6.REF_6") (pintype "bidirectional"))
      (node (ref "U4") (pin "1") (pinfunction "OUT1_1") (pintype "output"))
    )
    (net (code "43") (name "Net-(U$5-7.VOUT)") (class "Default")
      (node (ref "R16") (pin "1") (pinfunction "1_1") (pintype "passive"))
      (node (ref "R17") (pin "2") (pinfunction "2_2") (pintype "passive"))
      (node (ref "U$5") (pin "7") (pinfunction "7.VOUT_7") (pintype "bidirectional"))
    )
    (net (code "44") (name "Net-(U$12-2.C2P)") (class "Default")
      (node (ref "C35") (pin "2") (pinfunction "2_2") (pintype "passive"))
      (node (ref "U$12") (pin "P$2") (pinfunction "2.C2P_P$2") (pintype "bidirectional"))
    )
    (net (code "45") (name "Net-(U$12-3.C2N)") (class "Default")
      (node (ref "C35") (pin "1") (pinfunction "1_1") (pintype "passive"))
      (node (ref "U$12") (pin "P$3") (pinfunction "3.C2N_P$3") (pintype "bidirectional"))
    )
    (net (code "46") (name "Net-(U$12-4.C1P)") (class "Default")
      (node (ref "C36") (pin "2") (pinfunction "2_2") (pintype "passive"))
      (node (ref "U$12") (pin "P$4") (pinfunction "4.C1P_P$4") (pintype "bidirectional"))
    )
    (net (code "47") (name "Net-(U$12-5.C1N)") (class "Default")
      (node (ref "C36") (pin "1") (pinfunction "1_1") (pintype "passive"))
      (node (ref "U$12") (pin "P$5") (pinfunction "5.C1N_P$5") (pintype "bidirectional"))
    )
    (net (code "48") (name "Net-(U$12-14.RES#)") (class "Default")
      (node (ref "C34") (pin "2") (pinfunction "2_2") (pintype "passive"))
      (node (ref "R38") (pin "2") (pinfunction "2_2") (pintype "passive"))
      (node (ref "U$12") (pin "P$14") (pinfunction "14.RES#_P$14") (pintype "bidirectional"))
    )
    (net (code "49") (name "Net-(U$12-26.IREF)") (class "Default")
      (node (ref "R39") (pin "1") (pinfunction "1_1") (pintype "passive"))
      (node (ref "U$12") (pin "P$26") (pinfunction "26.IREF_P$26") (pintype "bidirectional"))
    )
    (net (code "50") (name "Net-(U$12-27.VCOMH)") (class "Default")
      (node (ref "C38") (pin "2") (pinfunction "2_2") (pintype "passive"))
      (node (ref "U$12") (pin "P$27") (pinfunction "27.VCOMH_P$27") (pintype "bidirectional"))
    )
    (net (code "51") (name "Net-(U$12-28.VCC)") (class "Default")
      (node (ref "C37") (pin "2") (pinfunction "2_2") (pintype "passive"))
      (node (ref "U$12") (pin "P$28") (pinfunction "28.VCC_P$28") (pintype "bidirectional"))
    )
    (net (code "52") (name "Net-(U1-IN+)") (class "Default")
      (node (ref "JP3") (pin "1") (pinfunction "1_1") (pintype "passive"))
      (node (ref "R14") (pin "2") (pinfunction "2_2") (pintype "passive"))
      (node (ref "U1") (pin "1") (pinfunction "IN+_1") (pintype "input"))
    )
    (net (code "53") (name "Net-(U3-IN+)") (class "Default")
      (node (ref "JP4") (pin "1") (pinfunction "1_1") (pintype "passive"))
      (node (ref "R15") (pin "2") (pinfunction "2_2") (pintype "passive"))
      (node (ref "U3") (pin "1") (pinfunction "IN+_1") (pintype "input"))
    )
    (net (code "54") (name "Net-(U4A-+IN1)") (class "Default")
      (node (ref "C25") (pin "1") (pinfunction "1_1") (pintype "passive"))
      (node (ref "R19") (pin "2") (pinfunction "2_2") (pintype "passive"))
      (node (ref "R20") (pin "1") (pinfunction "1_1") (pintype "passive"))
      (node (ref "R21") (pin "1") (pinfunction "1_1") (pintype "passive"))
      (node (ref "R22") (pin "1") (pinfunction "1_1") (pintype "passive"))
      (node (ref "U4") (pin "3") (pinfunction "+IN1_3") (pintype "input"))
      (node (ref "U4") (pin "5") (pinfunction "+IN2_5") (pintype "input"))
    )
    (net (code "55") (name "Net-(U4A--IN1)") (class "Default")
      (node (ref "C23") (pin "1") (pinfunction "1_1") (pintype "passive"))
      (node (ref "R16") (pin "2") (pinfunction "2_2") (pintype "passive"))
      (node (ref "U4") (pin "2") (pinfunction "-IN1_2") (pintype "input"))
    )
    (net (code "56") (name "Net-(U4B--IN2)") (class "Default")
      (node (ref "C24") (pin "2") (pinfunction "2_2") (pintype "passive"))
      (node (ref "R17") (pin "1") (pinfunction "1_1") (pintype "passive"))
      (node (ref "R18") (pin "2") (pinfunction "2_2") (pintype "passive"))
      (node (ref "U4") (pin "6") (pinfunction "-IN2_6") (pintype "input"))
    )
    (net (code "57") (name "Net-(U4B-OUT2)") (class "Default")
      (node (ref "C24") (pin "1") (pinfunction "1_1") (pintype "passive"))
      (node (ref "R18") (pin "1") (pinfunction "1_1") (pintype "passive"))
      (node (ref "R23") (pin "2") (pinfunction "2_2") (pintype "passive"))
      (node (ref "U4") (pin "7") (pinfunction "OUT2_7") (pintype "output"))
    )
    (net (code "58") (name "Net-(U5A-+IN1)") (class "Default")
      (node (ref "C28") (pin "2") (pinfunction "2_2") (pintype "passive"))
      (node (ref "R24") (pin "1") (pinfunction "1_1") (pintype "passive"))
      (node (ref "U5") (pin "3") (pinfunction "+IN1_3") (pintype "input"))
    )
    (net (code "59") (name "Net-(U5A--IN1)") (class "Default")
      (node (ref "R26") (pin "2") (pinfunction "2_2") (pintype "passive"))
      (node (ref "R27") (pin "2") (pinfunction "2_2") (pintype "passive"))
      (node (ref "U5") (pin "2") (pinfunction "-IN1_2") (pintype "input"))
    )
    (net (code "60") (name "Net-(U5A-OUT1)") (class "Default")
      (node (ref "R25") (pin "2") (pinfunction "2_2") (pintype "passive"))
      (node (ref "R27") (pin "1") (pinfunction "1_1") (pintype "passive"))
      (node (ref "U5") (pin "1") (pinfunction "OUT1_1") (pintype "output"))
      (node (ref "U5") (pin "5") (pinfunction "+IN2_5") (pintype "input"))
    )
    (net (code "61") (name "Net-(U5B--IN2)") (class "Default")
      (node (ref "R28") (pin "2") (pinfunction "2_2") (pintype "passive"))
      (node (ref "R29") (pin "2") (pinfunction "2_2") (pintype "passive"))
      (node (ref "U5") (pin "6") (pinfunction "-IN2_6") (pintype "input"))
    )
    (net (code "62") (name "Net-(U5B-OUT2)") (class "Default")
      (node (ref "R29") (pin "1") (pinfunction "1_1") (pintype "passive"))
      (node (ref "R30") (pin "1") (pinfunction "1_1") (pintype "passive"))
      (node (ref "U5") (pin "7") (pinfunction "OUT2_7") (pintype "output"))
    )
    (net (code "63") (name "Net-(U5C-+IN2)") (class "Default")
      (node (ref "C29") (pin "1") (pinfunction "1_1") (pintype "passive"))
      (node (ref "R31") (pin "2") (pinfunction "2_2") (pintype "passive"))
      (node (ref "U5") (pin "10") (pinfunction "+IN2_10") (pintype "input"))
    )
    (net (code "64") (name "Net-(U5C--IN2)") (class "Default")
      (node (ref "R32") (pin "2") (pinfunction "2_2") (pintype "passive"))
      (node (ref "R33") (pin "1") (pinfunction "1_1") (pintype "passive"))
      (node (ref "U5") (pin "9") (pinfunction "-IN2_9") (pintype "input"))
    )
    (net (code "65") (name "Net-(U5C-OUT2)") (class "Default")
      (node (ref "C30") (pin "2") (pinfunction "2_2") (pintype "passive"))
      (node (ref "C32") (pin "1") (pinfunction "1_1") (pintype "passive"))
      (node (ref "R33") (pin "2") (pinfunction "2_2") (pintype "passive"))
      (node (ref "R34") (pin "1") (pinfunction "1_1") (pintype "passive"))
      (node (ref "U5") (pin "8") (pinfunction "OUT2_8") (pintype "output"))
    )
    (net (code "66") (name "Net-(U5D-+IN2)") (class "Default")
      (node (ref "C31") (pin "2") (pinfunction "2_2") (pintype "passive"))
      (node (ref "R35") (pin "2") (pinfunction "2_2") (pintype "passive"))
      (node (ref "U5") (pin "12") (pinfunction "+IN2_12") (pintype "input"))
    )
    (net (code "67") (name "Net-(U5D--IN2)") (class "Default")
      (node (ref "R37") (pin "1") (pinfunction "1_1") (pintype "passive"))
      (node (ref "U5") (pin "13") (pinfunction "-IN2_13") (pintype "input"))
    )
    (net (code "68") (name "VCC") (class "Default")
      (node (ref "C1") (pin "2") (pinfunction "2_2") (pintype "passive"))
      (node (ref "IC2") (pin "3") (pinfunction "IN_3") (pintype "input"))
      (node (ref "JP1") (pin "1") (pinfunction "1_1") (pintype "passive"))
      (node (ref "JP2") (pin "1") (pinfunction "1_1") (pintype "passive"))
      (node (ref "U2") (pin "VBUS1") (pinfunction "VBUS_VBUS1") (pintype "bidirectional"))
    )
    (net (code "69") (name "VDD") (class "Default")
      (node (ref "C2") (pin "2") (pinfunction "2_2") (pintype "passive"))
      (node (ref "C3") (pin "2") (pinfunction "2_2") (pintype "passive"))
      (node (ref "IC1") (pin "1") (pinfunction "VIN_1") (pintype "input"))
      (node (ref "IC1") (pin "3") (pinfunction "VINH_3") (pintype "input"))
      (node (ref "IC2") (pin "2") (pinfunction "OUT_2") (pintype "output"))
      (node (ref "IC2") (pin "4") (pinfunction "OUT_4") (pintype "output"))
      (node (ref "R38") (pin "1") (pinfunction "1_1") (pintype "passive"))
      (node (ref "R40") (pin "2") (pinfunction "2_2") (pintype "passive"))
      (node (ref "R41") (pin "1") (pinfunction "1_1") (pintype "passive"))
      (node (ref "U$12") (pin "P$11") (pinfunction "11.BS1_P$11") (pintype "bidirectional"))
      (node (ref "U$12") (pin "P$6") (pinfunction "6.VBAT_P$6") (pintype "bidirectional"))
      (node (ref "U$12") (pin "P$9") (pinfunction "9.VDD_P$9") (pintype "bidirectional"))
    )
    (net (code "70") (name "unconnected-(R1-CW-Pad3)") (class "Default")
      (node (ref "R1") (pin "3") (pinfunction "CW_3") (pintype "passive"))
    )
    (net (code "71") (name "unconnected-(R2-CW-Pad3)") (class "Default")
      (node (ref "R2") (pin "3") (pinfunction "CW_3") (pintype "passive"))
    )
    (net (code "72") (name "unconnected-(R3-CCW-Pad1)") (class "Default")
      (node (ref "R3") (pin "1") (pinfunction "CCW_1") (pintype "passive"))
    )
    (net (code "73") (name "unconnected-(U$1-PA0{slash}ETH_MII_CRS{slash}ADC123_IN0(5T)-Pad23)") (class "Default")
      (node (ref "U$1") (pin "23") (pinfunction "PA0/ETH_MII_CRS/ADC123_IN0(5T)_23") (pintype "bidirectional"))
    )
    (net (code "74") (name "unconnected-(U$1-PA1{slash}ETH_RMII_RX_CLK{slash}ADC123_IN1(5T)-Pad24)") (class "Default")
      (node (ref "U$1") (pin "24") (pinfunction "PA1/ETH_RMII_RX_CLK/ADC123_IN1(5T)_24") (pintype "bidirectional"))
    )
    (net (code "75") (name "unconnected-(U$1-PA4{slash}ADC12_IN4-Pad29)") (class "Default")
      (node (ref "U$1") (pin "29") (pinfunction "PA4/ADC12_IN4_29") (pintype "bidirectional"))
    )
    (net (code "76") (name "unconnected-(U$1-PA5{slash}SPI1_SCK{slash}ADC12_IN5-Pad30)") (class "Default")
      (node (ref "U$1") (pin "30") (pinfunction "PA5/SPI1_SCK/ADC12_IN5_30") (pintype "bidirectional"))
    )
    (net (code "77") (name "unconnected-(U$1-PA6{slash}SPI1_MISO{slash}ADC12_IN6(5T)-Pad31)") (class "Default")
      (node (ref "U$1") (pin "31") (pinfunction "PA6/SPI1_MISO/ADC12_IN6(5T)_31") (pintype "bidirectional"))
    )
    (net (code "78") (name "unconnected-(U$1-PA7{slash}ETH_MII_RX_DV{slash}ADC12_IN7(5T)-Pad32)") (class "Default")
      (node (ref "U$1") (pin "32") (pinfunction "PA7/ETH_MII_RX_DV/ADC12_IN7(5T)_32") (pintype "bidirectional"))
    )
    (net (code "79") (name "unconnected-(U$1-PA9{slash}USART1_TX(5T)-Pad68)") (class "Default")
      (node (ref "U$1") (pin "68") (pinfunction "PA9/USART1_TX(5T)_68") (pintype "bidirectional"))
    )
    (net (code "80") (name "unconnected-(U$1-PA10{slash}USART1_RX(5T)-Pad69)") (class "Default")
      (node (ref "U$1") (pin "69") (pinfunction "PA10/USART1_RX(5T)_69") (pintype "bidirectional"))
    )
    (net (code "81") (name "unconnected-(U$1-PA11{slash}USART1_CTS(5T)-Pad70)") (class "Default")
      (node (ref "U$1") (pin "70") (pinfunction "PA11/USART1_CTS(5T)_70") (pintype "bidirectional"))
    )
    (net (code "82") (name "unconnected-(U$1-PA12{slash}USART1_RTS(5T)-Pad71)") (class "Default")
      (node (ref "U$1") (pin "71") (pinfunction "PA12/USART1_RTS(5T)_71") (pintype "bidirectional"))
    )
    (net (code "83") (name "unconnected-(U$1-PA15{slash}JTDI(5T)-Pad77)") (class "Default")
      (node (ref "U$1") (pin "77") (pinfunction "PA15/JTDI(5T)_77") (pintype "bidirectional"))
    )
    (net (code "84") (name "unconnected-(U$1-PB0{slash}ETH_MII_RXD2{slash}ADC12_IN8(5T)-Pad35)") (class "Default")
      (node (ref "U$1") (pin "35") (pinfunction "PB0/ETH_MII_RXD2/ADC12_IN8(5T)_35") (pintype "bidirectional"))
    )
    (net (code "85") (name "unconnected-(U$1-PB1{slash}ETH_MII_RXD3{slash}ADC12_IN9(5T)-Pad36)") (class "Default")
      (node (ref "U$1") (pin "36") (pinfunction "PB1/ETH_MII_RXD3/ADC12_IN9(5T)_36") (pintype "bidirectional"))
    )
    (net (code "86") (name "unconnected-(U$1-PB2{slash}BOOT1(5T)-Pad37)") (class "Default")
      (node (ref "U$1") (pin "37") (pinfunction "PB2/BOOT1(5T)_37") (pintype "bidirectional"))
    )
    (net (code "87") (name "unconnected-(U$1-PB3{slash}JTDO(5T)-Pad89)") (class "Default")
      (node (ref "U$1") (pin "89") (pinfunction "PB3/JTDO(5T)_89") (pintype "bidirectional"))
    )
    (net (code "88") (name "unconnected-(U$1-PB4{slash}JNTRST(5T)-Pad90)") (class "Default")
      (node (ref "U$1") (pin "90") (pinfunction "PB4/JNTRST(5T)_90") (pintype "bidirectional"))
    )
    (net (code "89") (name "unconnected-(U$1-PB8{slash}TIM10_CH1(5T)-Pad95)") (class "Default")
      (node (ref "U$1") (pin "95") (pinfunction "PB8/TIM10_CH1(5T)_95") (pintype "bidirectional"))
    )
    (net (code "90") (name "unconnected-(U$1-PB9{slash}TIM11_CH1(5T)-Pad96)") (class "Default")
      (node (ref "U$1") (pin "96") (pinfunction "PB9/TIM11_CH1(5T)_96") (pintype "bidirectional"))
    )
    (net (code "91") (name "unconnected-(U$1-PB13{slash}ETH_MII_TXD1(5T)-Pad52)") (class "Default")
      (node (ref "U$1") (pin "52") (pinfunction "PB13/ETH_MII_TXD1(5T)_52") (pintype "bidirectional"))
    )
    (net (code "92") (name "unconnected-(U$1-PB14{slash}TIM8_CH2N(5T)-Pad53)") (class "Default")
      (node (ref "U$1") (pin "53") (pinfunction "PB14/TIM8_CH2N(5T)_53") (pintype "bidirectional"))
    )
    (net (code "93") (name "unconnected-(U$1-PB15{slash}TIM8_CH3N(5T)-Pad54)") (class "Default")
      (node (ref "U$1") (pin "54") (pinfunction "PB15/TIM8_CH3N(5T)_54") (pintype "bidirectional"))
    )
    (net (code "94") (name "unconnected-(U$1-PC3{slash}ETH_MII_TX_CLK{slash}ADC123_IN13(5T)-Pad18)") (class "Default")
      (node (ref "U$1") (pin "18") (pinfunction "PC3/ETH_MII_TX_CLK/ADC123_IN13(5T)_18") (pintype "bidirectional"))
    )
    (net (code "95") (name "unconnected-(U$1-PC4{slash}ETH_MII_RXD0{slash}ADC12_IN14(5T)-Pad33)") (class "Default")
      (node (ref "U$1") (pin "33") (pinfunction "PC4/ETH_MII_RXD0/ADC12_IN14(5T)_33") (pintype "bidirectional"))
    )
    (net (code "96") (name "unconnected-(U$1-PC5{slash}ETH_MII_RXD1{slash}ADC12_IN15(5T)-Pad34)") (class "Default")
      (node (ref "U$1") (pin "34") (pinfunction "PC5/ETH_MII_RXD1/ADC12_IN15(5T)_34") (pintype "bidirectional"))
    )
    (net (code "97") (name "unconnected-(U$1-PC6{slash}TIM3_CH1(5T)-Pad63)") (class "Default")
      (node (ref "U$1") (pin "63") (pinfunction "PC6/TIM3_CH1(5T)_63") (pintype "bidirectional"))
    )
    (net (code "98") (name "unconnected-(U$1-PC7{slash}TIM8_CH2(5T)-Pad64)") (class "Default")
      (node (ref "U$1") (pin "64") (pinfunction "PC7/TIM8_CH2(5T)_64") (pintype "bidirectional"))
    )
    (net (code "99") (name "unconnected-(U$1-PC8{slash}TIM8_CH3(5T)-Pad65)") (class "Default")
      (node (ref "U$1") (pin "65") (pinfunction "PC8/TIM8_CH3(5T)_65") (pintype "bidirectional"))
    )
    (net (code "100") (name "unconnected-(U$1-PC10{slash}UART4_TX(5T)-Pad78)") (class "Default")
      (node (ref "U$1") (pin "78") (pinfunction "PC10/UART4_TX(5T)_78") (pintype "bidirectional"))
    )
    (net (code "101") (name "unconnected-(U$1-PC11{slash}UART4_RX(5T)-Pad79)") (class "Default")
      (node (ref "U$1") (pin "79") (pinfunction "PC11/UART4_RX(5T)_79") (pintype "bidirectional"))
    )
    (net (code "102") (name "unconnected-(U$1-PC12{slash}UART5_TX(5T)-Pad80)") (class "Default")
      (node (ref "U$1") (pin "80") (pinfunction "PC12/UART5_TX(5T)_80") (pintype "bidirectional"))
    )
    (net (code "103") (name "unconnected-(U$1-PC13(5T)-Pad7)") (class "Default")
      (node (ref "U$1") (pin "7") (pinfunction "PC13(5T)_7") (pintype "bidirectional"))
    )
    (net (code "104") (name "unconnected-(U$1-PD0{slash}CAN1_RX(5T)-Pad81)") (class "Default")
      (node (ref "U$1") (pin "81") (pinfunction "PD0/CAN1_RX(5T)_81") (pintype "bidirectional"))
    )
    (net (code "105") (name "unconnected-(U$1-PD1{slash}CAN1_TX(5T)-Pad82)") (class "Default")
      (node (ref "U$1") (pin "82") (pinfunction "PD1/CAN1_TX(5T)_82") (pintype "bidirectional"))
    )
    (net (code "106") (name "unconnected-(U$1-PD2{slash}UART5_RX(5T)-Pad83)") (class "Default")
      (node (ref "U$1") (pin "83") (pinfunction "PD2/UART5_RX(5T)_83") (pintype "bidirectional"))
    )
    (net (code "107") (name "unconnected-(U$1-PD3(5T)-Pad84)") (class "Default")
      (node (ref "U$1") (pin "84") (pinfunction "PD3(5T)_84") (pintype "bidirectional"))
    )
    (net (code "108") (name "unconnected-(U$1-PD4(5T)-Pad85)") (class "Default")
      (node (ref "U$1") (pin "85") (pinfunction "PD4(5T)_85") (pintype "bidirectional"))
    )
    (net (code "109") (name "unconnected-(U$1-PD5{slash}USART2_TX(5T)-Pad86)") (class "Default")
      (node (ref "U$1") (pin "86") (pinfunction "PD5/USART2_TX(5T)_86") (pintype "bidirectional"))
    )
    (net (code "110") (name "unconnected-(U$1-PD6{slash}USART2_RX(5T)-Pad87)") (class "Default")
      (node (ref "U$1") (pin "87") (pinfunction "PD6/USART2_RX(5T)_87") (pintype "bidirectional"))
    )
    (net (code "111") (name "unconnected-(U$1-PD7(5T)-Pad88)") (class "Default")
      (node (ref "U$1") (pin "88") (pinfunction "PD7(5T)_88") (pintype "bidirectional"))
    )
    (net (code "112") (name "unconnected-(U$1-PD8{slash}USART3_TX(5T)-Pad55)") (class "Default")
      (node (ref "U$1") (pin "55") (pinfunction "PD8/USART3_TX(5T)_55") (pintype "bidirectional"))
    )
    (net (code "113") (name "unconnected-(U$1-PD9{slash}USART3_RX(5T)-Pad56)") (class "Default")
      (node (ref "U$1") (pin "56") (pinfunction "PD9/USART3_RX(5T)_56") (pintype "bidirectional"))
    )
    (net (code "114") (name "unconnected-(U$1-PD10(5T)-Pad57)") (class "Default")
      (node (ref "U$1") (pin "57") (pinfunction "PD10(5T)_57") (pintype "bidirectional"))
    )
    (net (code "115") (name "unconnected-(U$1-PD11(5T)-Pad58)") (class "Default")
      (node (ref "U$1") (pin "58") (pinfunction "PD11(5T)_58") (pintype "bidirectional"))
    )
    (net (code "116") (name "unconnected-(U$1-PD12{slash}TIM4_CH1(5T)-Pad59)") (class "Default")
      (node (ref "U$1") (pin "59") (pinfunction "PD12/TIM4_CH1(5T)_59") (pintype "bidirectional"))
    )
    (net (code "117") (name "unconnected-(U$1-PD13{slash}TIM4_CH2(5T)-Pad60)") (class "Default")
      (node (ref "U$1") (pin "60") (pinfunction "PD13/TIM4_CH2(5T)_60") (pintype "bidirectional"))
    )
    (net (code "118") (name "unconnected-(U$1-PD14{slash}TIM4_CH3(5T)-Pad61)") (class "Default")
      (node (ref "U$1") (pin "61") (pinfunction "PD14/TIM4_CH3(5T)_61") (pintype "bidirectional"))
    )
    (net (code "119") (name "unconnected-(U$1-PD15{slash}TIM4_CH4(5T)-Pad62)") (class "Default")
      (node (ref "U$1") (pin "62") (pinfunction "PD15/TIM4_CH4(5T)_62") (pintype "bidirectional"))
    )
    (net (code "120") (name "unconnected-(U$1-PE0(5T)-Pad97)") (class "Default")
      (node (ref "U$1") (pin "97") (pinfunction "PE0(5T)_97") (pintype "bidirectional"))
    )
    (net (code "121") (name "unconnected-(U$1-PE1(5T)-Pad98)") (class "Default")
      (node (ref "U$1") (pin "98") (pinfunction "PE1(5T)_98") (pintype "bidirectional"))
    )
    (net (code "122") (name "unconnected-(U$1-PE2{slash}ETH_MII_TXD3(5T)-Pad1)") (class "Default")
      (node (ref "U$1") (pin "1") (pinfunction "PE2/ETH_MII_TXD3(5T)_1") (pintype "bidirectional"))
    )
    (net (code "123") (name "unconnected-(U$1-PE3(5T)-Pad2)") (class "Default")
      (node (ref "U$1") (pin "2") (pinfunction "PE3(5T)_2") (pintype "bidirectional"))
    )
    (net (code "124") (name "unconnected-(U$1-PE4(5T)-Pad3)") (class "Default")
      (node (ref "U$1") (pin "3") (pinfunction "PE4(5T)_3") (pintype "bidirectional"))
    )
    (net (code "125") (name "unconnected-(U$1-PE5{slash}TIM9_CH1(5T)-Pad4)") (class "Default")
      (node (ref "U$1") (pin "4") (pinfunction "PE5/TIM9_CH1(5T)_4") (pintype "bidirectional"))
    )
    (net (code "126") (name "unconnected-(U$1-PE6{slash}TIM9_CH2(5T)-Pad5)") (class "Default")
      (node (ref "U$1") (pin "5") (pinfunction "PE6/TIM9_CH2(5T)_5") (pintype "bidirectional"))
    )
    (net (code "127") (name "unconnected-(U$1-PE7{slash}TIM1_ETR(5T)-Pad38)") (class "Default")
      (node (ref "U$1") (pin "38") (pinfunction "PE7/TIM1_ETR(5T)_38") (pintype "bidirectional"))
    )
    (net (code "128") (name "unconnected-(U$1-PE8{slash}TIM1_CH1N(5T)-Pad39)") (class "Default")
      (node (ref "U$1") (pin "39") (pinfunction "PE8/TIM1_CH1N(5T)_39") (pintype "bidirectional"))
    )
    (net (code "129") (name "unconnected-(U$1-PE9{slash}TIM1_CH1(5T)-Pad40)") (class "Default")
      (node (ref "U$1") (pin "40") (pinfunction "PE9/TIM1_CH1(5T)_40") (pintype "bidirectional"))
    )
    (net (code "130") (name "unconnected-(U$1-PE10{slash}TIM1_CH2N(5T)-Pad41)") (class "Default")
      (node (ref "U$1") (pin "41") (pinfunction "PE10/TIM1_CH2N(5T)_41") (pintype "bidirectional"))
    )
    (net (code "131") (name "unconnected-(U$1-PE11{slash}TIM1_CH2(5T)-Pad42)") (class "Default")
      (node (ref "U$1") (pin "42") (pinfunction "PE11/TIM1_CH2(5T)_42") (pintype "bidirectional"))
    )
    (net (code "132") (name "unconnected-(U$1-PE12{slash}TIM1_CH3N(5T)-Pad43)") (class "Default")
      (node (ref "U$1") (pin "43") (pinfunction "PE12/TIM1_CH3N(5T)_43") (pintype "bidirectional"))
    )
    (net (code "133") (name "unconnected-(U$1-PE13{slash}TIM1_CH3(5T)-Pad44)") (class "Default")
      (node (ref "U$1") (pin "44") (pinfunction "PE13/TIM1_CH3(5T)_44") (pintype "bidirectional"))
    )
    (net (code "134") (name "unconnected-(U$1-PE14{slash}TIM1_CH4(5T)-Pad45)") (class "Default")
      (node (ref "U$1") (pin "45") (pinfunction "PE14/TIM1_CH4(5T)_45") (pintype "bidirectional"))
    )
    (net (code "135") (name "unconnected-(U$1-PE15{slash}TIM1_BKIN(5T)-Pad46)") (class "Default")
      (node (ref "U$1") (pin "46") (pinfunction "PE15/TIM1_BKIN(5T)_46") (pintype "bidirectional"))
    )
    (net (code "136") (name "unconnected-(U$10-IR_DRV-Pad5)") (class "Default")
      (node (ref "U$10") (pin "5") (pinfunction "IR_DRV_5") (pintype "bidirectional"))
    )
    (net (code "137") (name "unconnected-(U$10-R_DRV-Pad6)") (class "Default")
      (node (ref "U$10") (pin "6") (pinfunction "R_DRV_6") (pintype "bidirectional"))
    )
    (net (code "138") (name "unconnected-(U$11-IR_DRV-Pad5)") (class "Default")
      (node (ref "U$11") (pin "5") (pinfunction "IR_DRV_5") (pintype "bidirectional"))
    )
    (net (code "139") (name "unconnected-(U$11-R_DRV-Pad6)") (class "Default")
      (node (ref "U$11") (pin "6") (pinfunction "R_DRV_6") (pintype "bidirectional"))
    )
    (net (code "140") (name "unconnected-(U$12-1.NC(GND)-PadP$1)") (class "Default")
      (node (ref "U$12") (pin "P$1") (pinfunction "1.NC(GND)_P$1") (pintype "bidirectional"))
    )
    (net (code "141") (name "unconnected-(U$12-7.NC-PadP$7)") (class "Default")
      (node (ref "U$12") (pin "P$7") (pinfunction "7.NC_P$7") (pintype "bidirectional"))
    )
    (net (code "142") (name "unconnected-(U$12-30.NC(GND)-PadP$30)") (class "Default")
      (node (ref "U$12") (pin "P$30") (pinfunction "30.NC(GND)_P$30") (pintype "bidirectional"))
    )
    (net (code "143") (name "unconnected-(U2-D+-PadD+1)") (class "Default")
      (node (ref "U2") (pin "D+1") (pinfunction "D+_D+1") (pintype "bidirectional"))
    )
    (net (code "144") (name "unconnected-(U2-D--PadD-1)") (class "Default")
      (node (ref "U2") (pin "D-1") (pinfunction "D-_D-1") (pintype "bidirectional"))
    )
    (net (code "145") (name "unconnected-(U2-USBID-PadID1)") (class "Default")
      (node (ref "U2") (pin "ID1") (pinfunction "USBID_ID1") (pintype "bidirectional"))
    )
    (net (code "146") (name "unconnected-(U4C-+IN2-Pad10)") (class "Default")
      (node (ref "U4") (pin "10") (pinfunction "+IN2_10") (pintype "input"))
    )
    (net (code "147") (name "unconnected-(U4C--IN2-Pad9)") (class "Default")
      (node (ref "U4") (pin "9") (pinfunction "-IN2_9") (pintype "input"))
    )
    (net (code "148") (name "unconnected-(U4C-OUT2-Pad8)") (class "Default")
      (node (ref "U4") (pin "8") (pinfunction "OUT2_8") (pintype "output"))
    )
    (net (code "149") (name "unconnected-(U4D-+IN2-Pad12)") (class "Default")
      (node (ref "U4") (pin "12") (pinfunction "+IN2_12") (pintype "input"))
    )
    (net (code "150") (name "unconnected-(U4D--IN2-Pad13)") (class "Default")
      (node (ref "U4") (pin "13") (pinfunction "-IN2_13") (pintype "input"))
    )
    (net (code "151") (name "unconnected-(U4D-OUT2-Pad14)") (class "Default")
      (node (ref "U4") (pin "14") (pinfunction "OUT2_14") (pintype "output"))
    )
  )
)
